# base.net
KiCad netlist of a schematic drawn in EAGLE
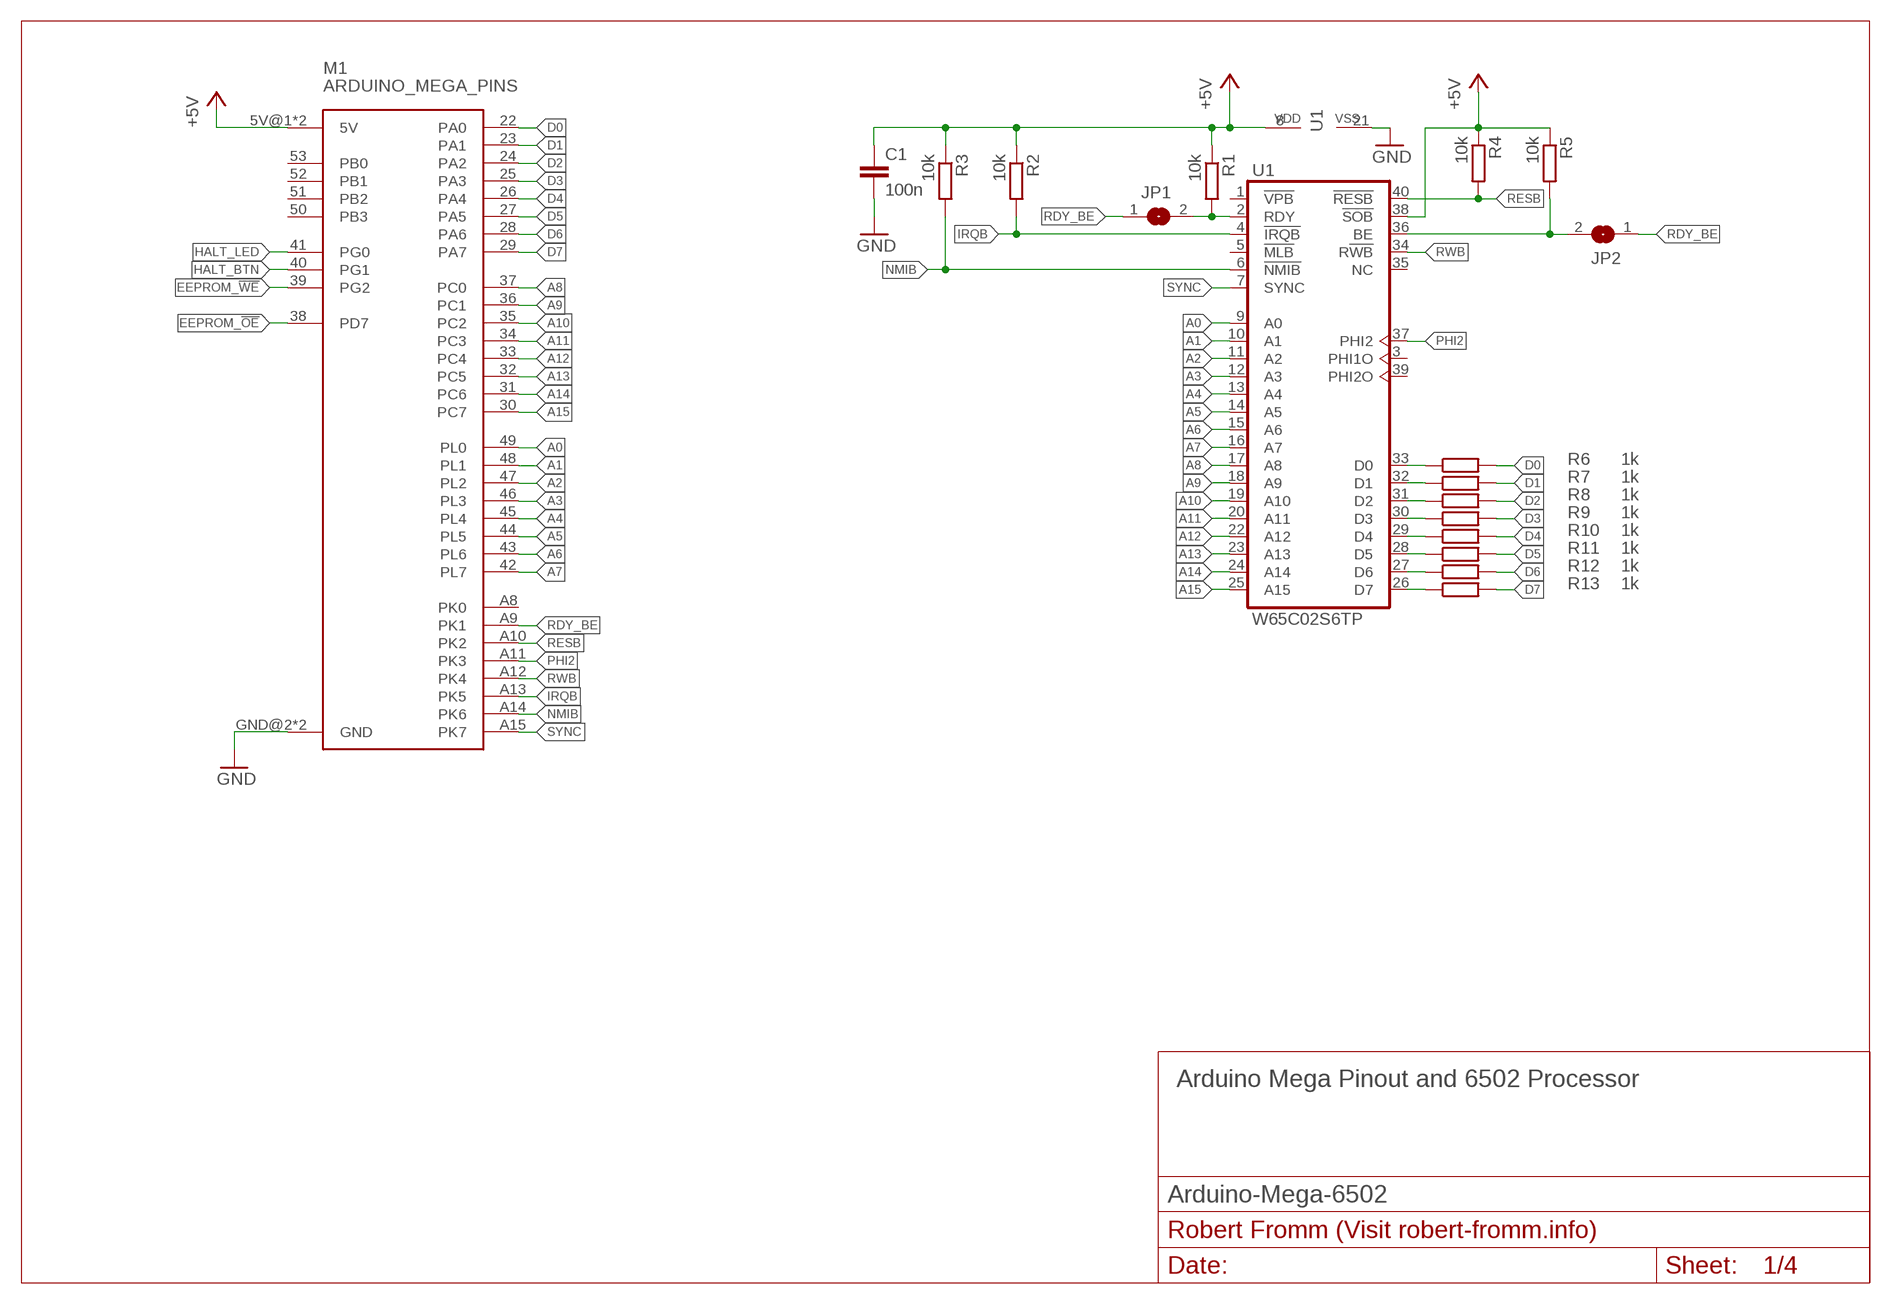
[diagram p0: schematic, sheet 1]
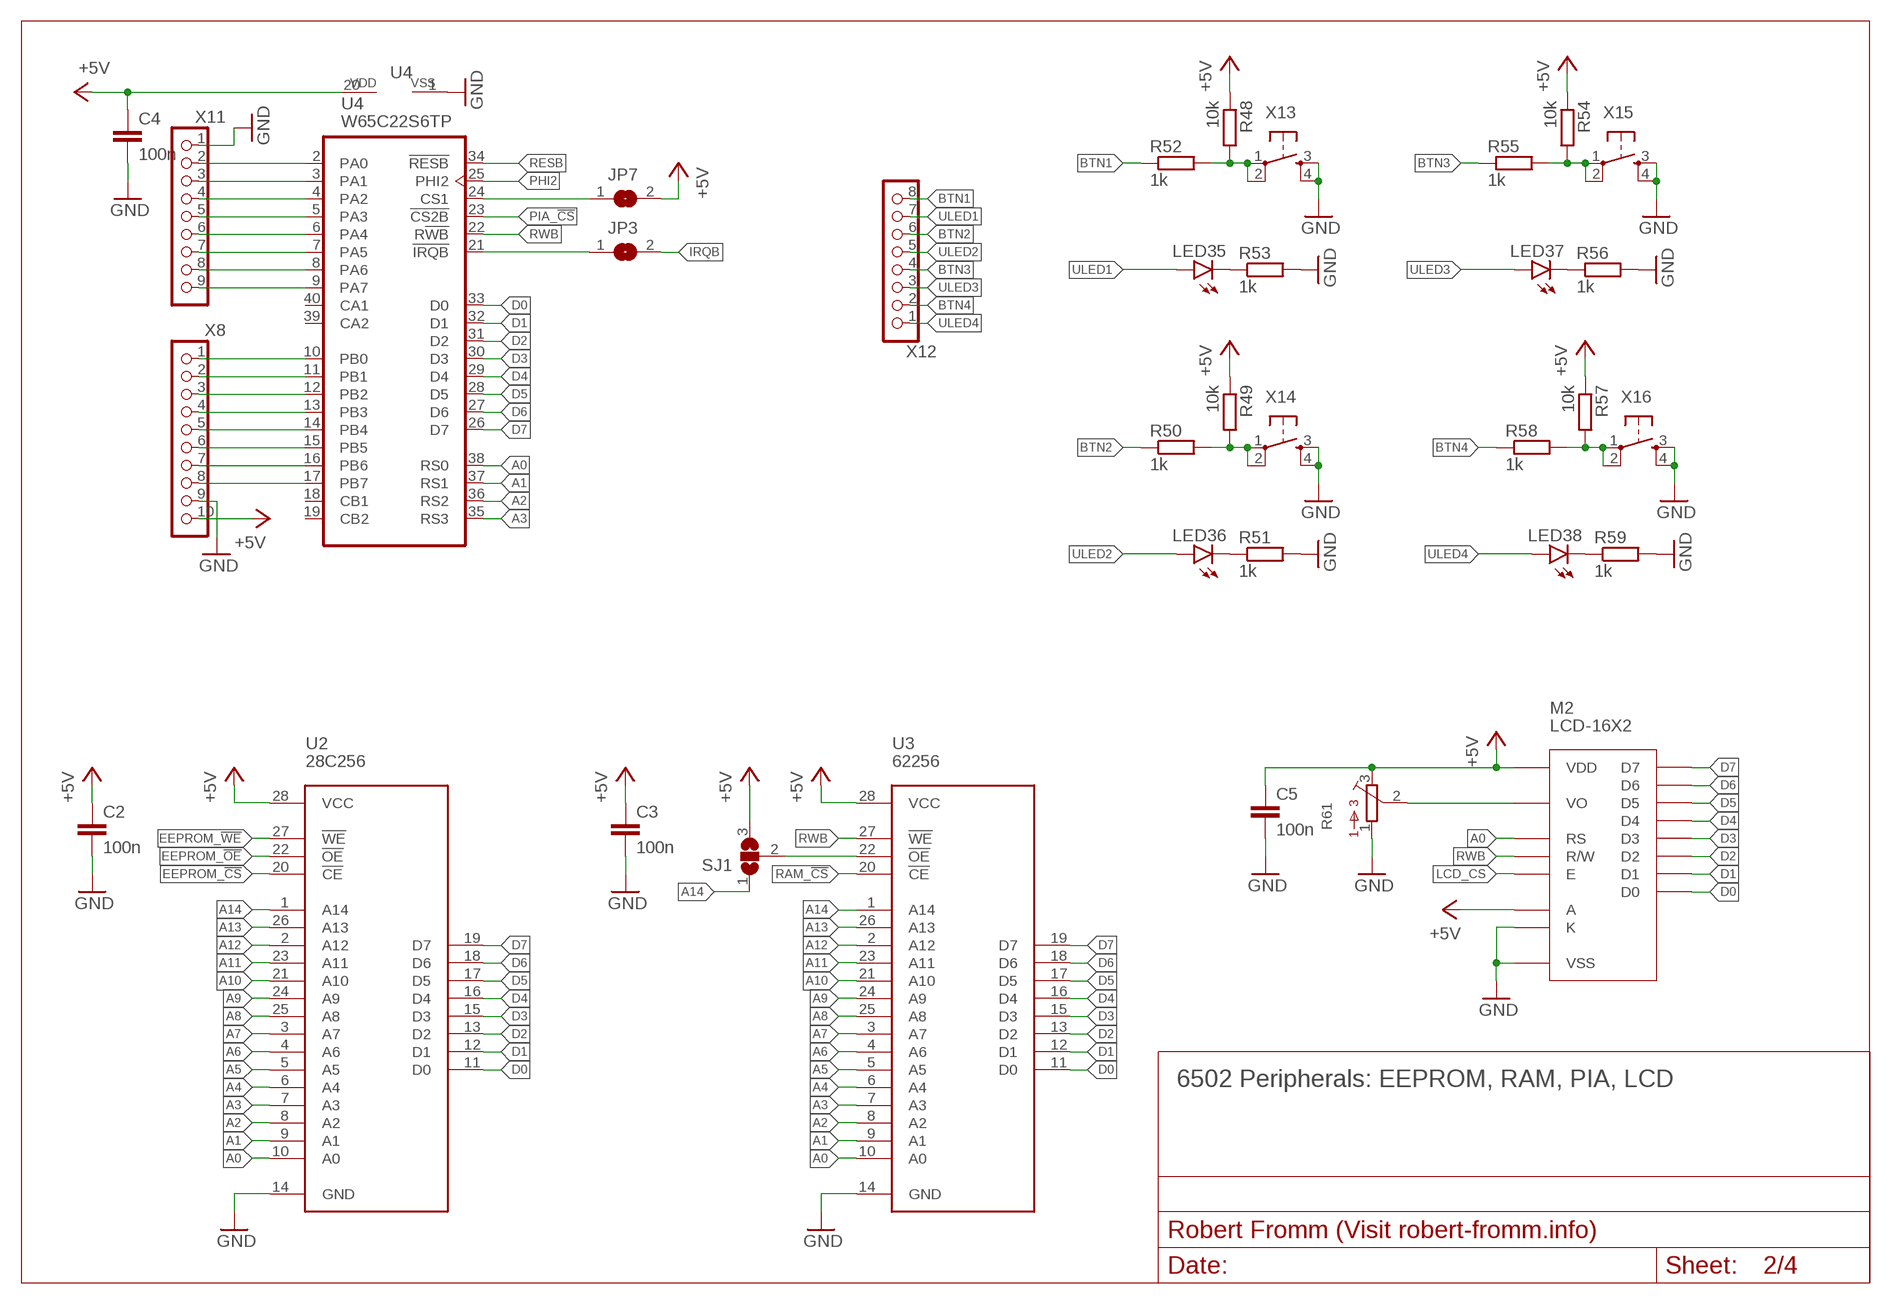
[diagram p1: schematic, sheet 2]
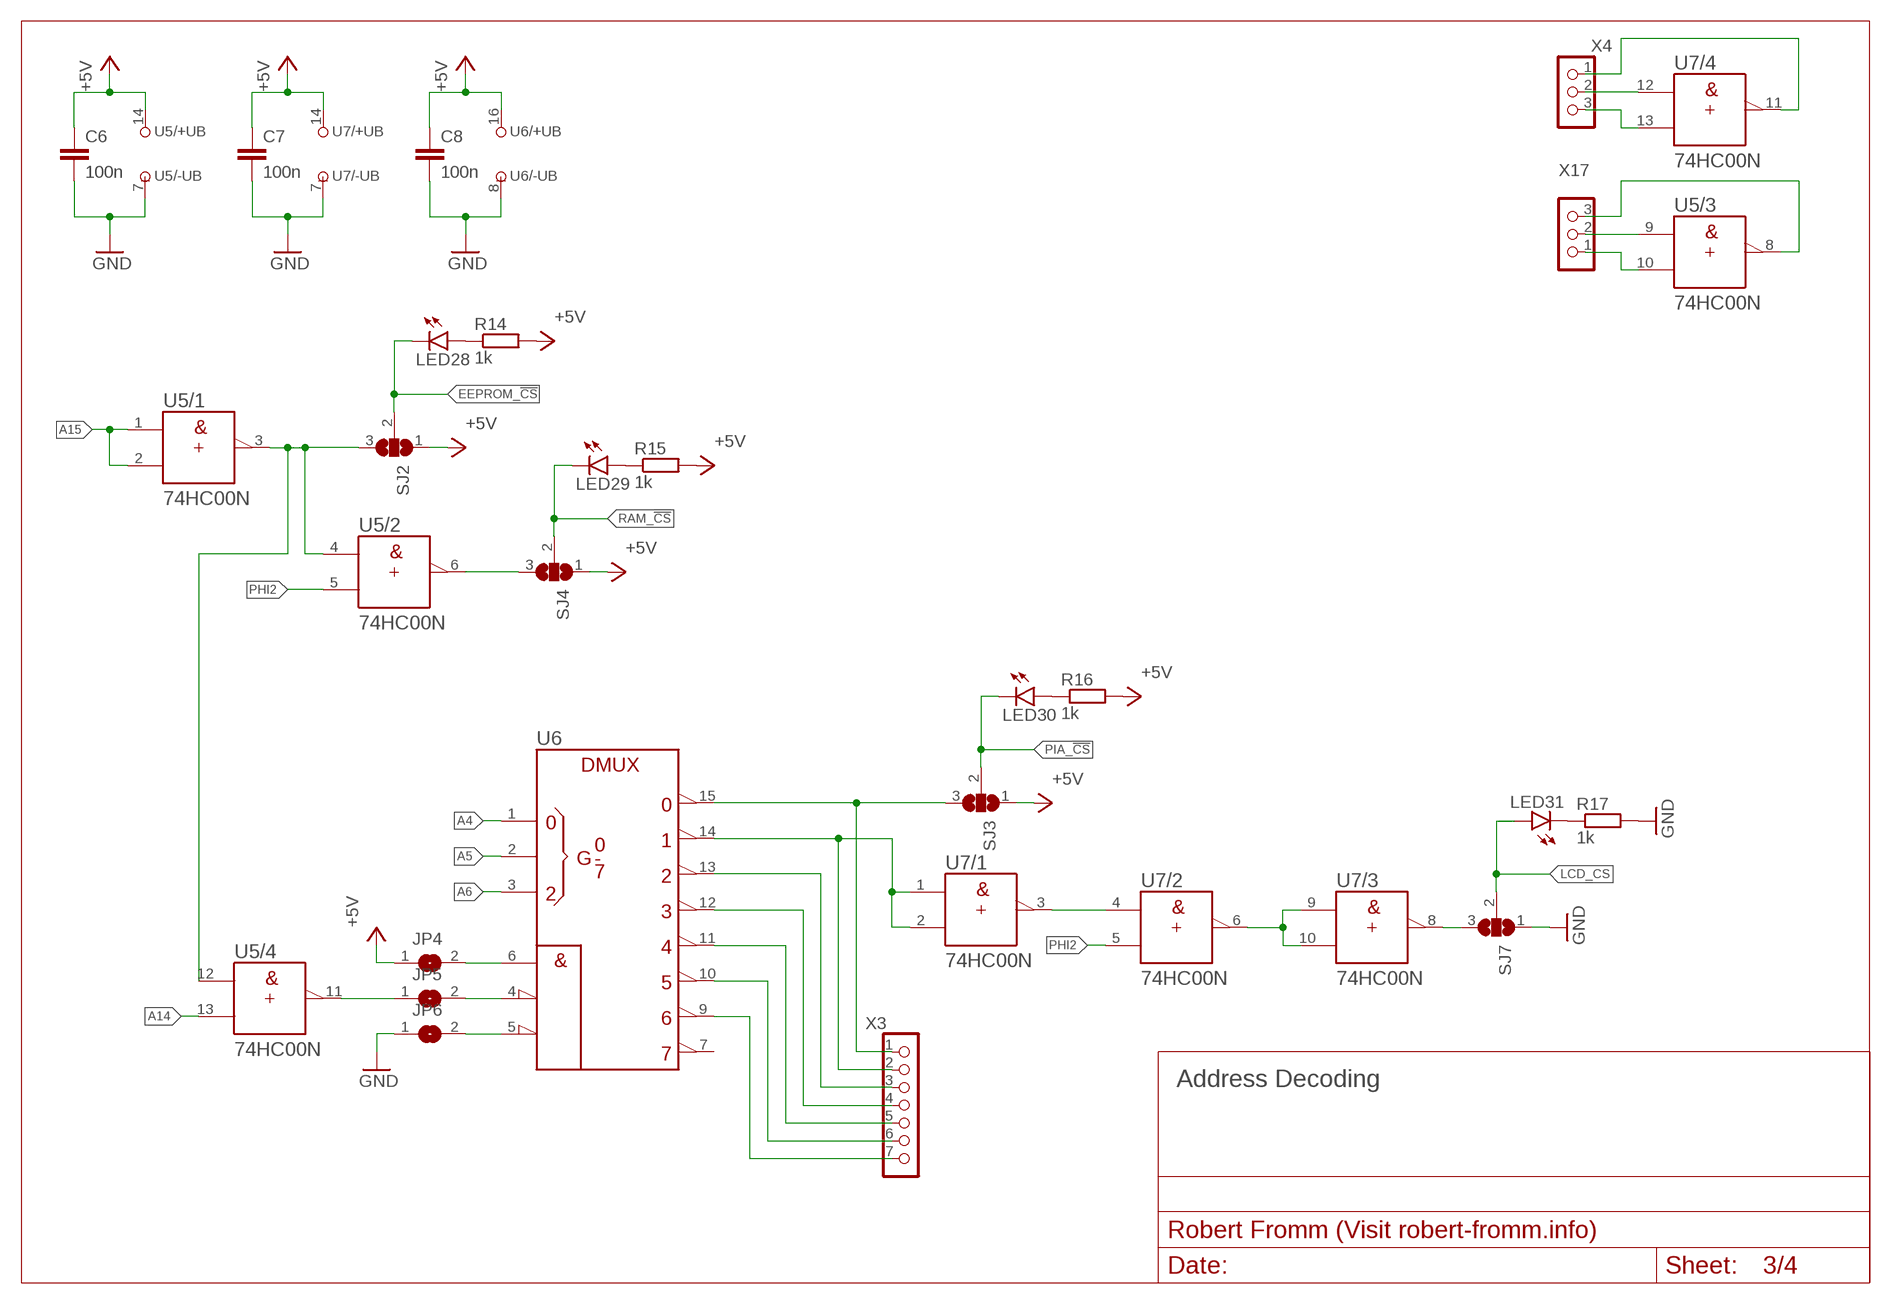
[diagram p2: schematic, sheet 3]
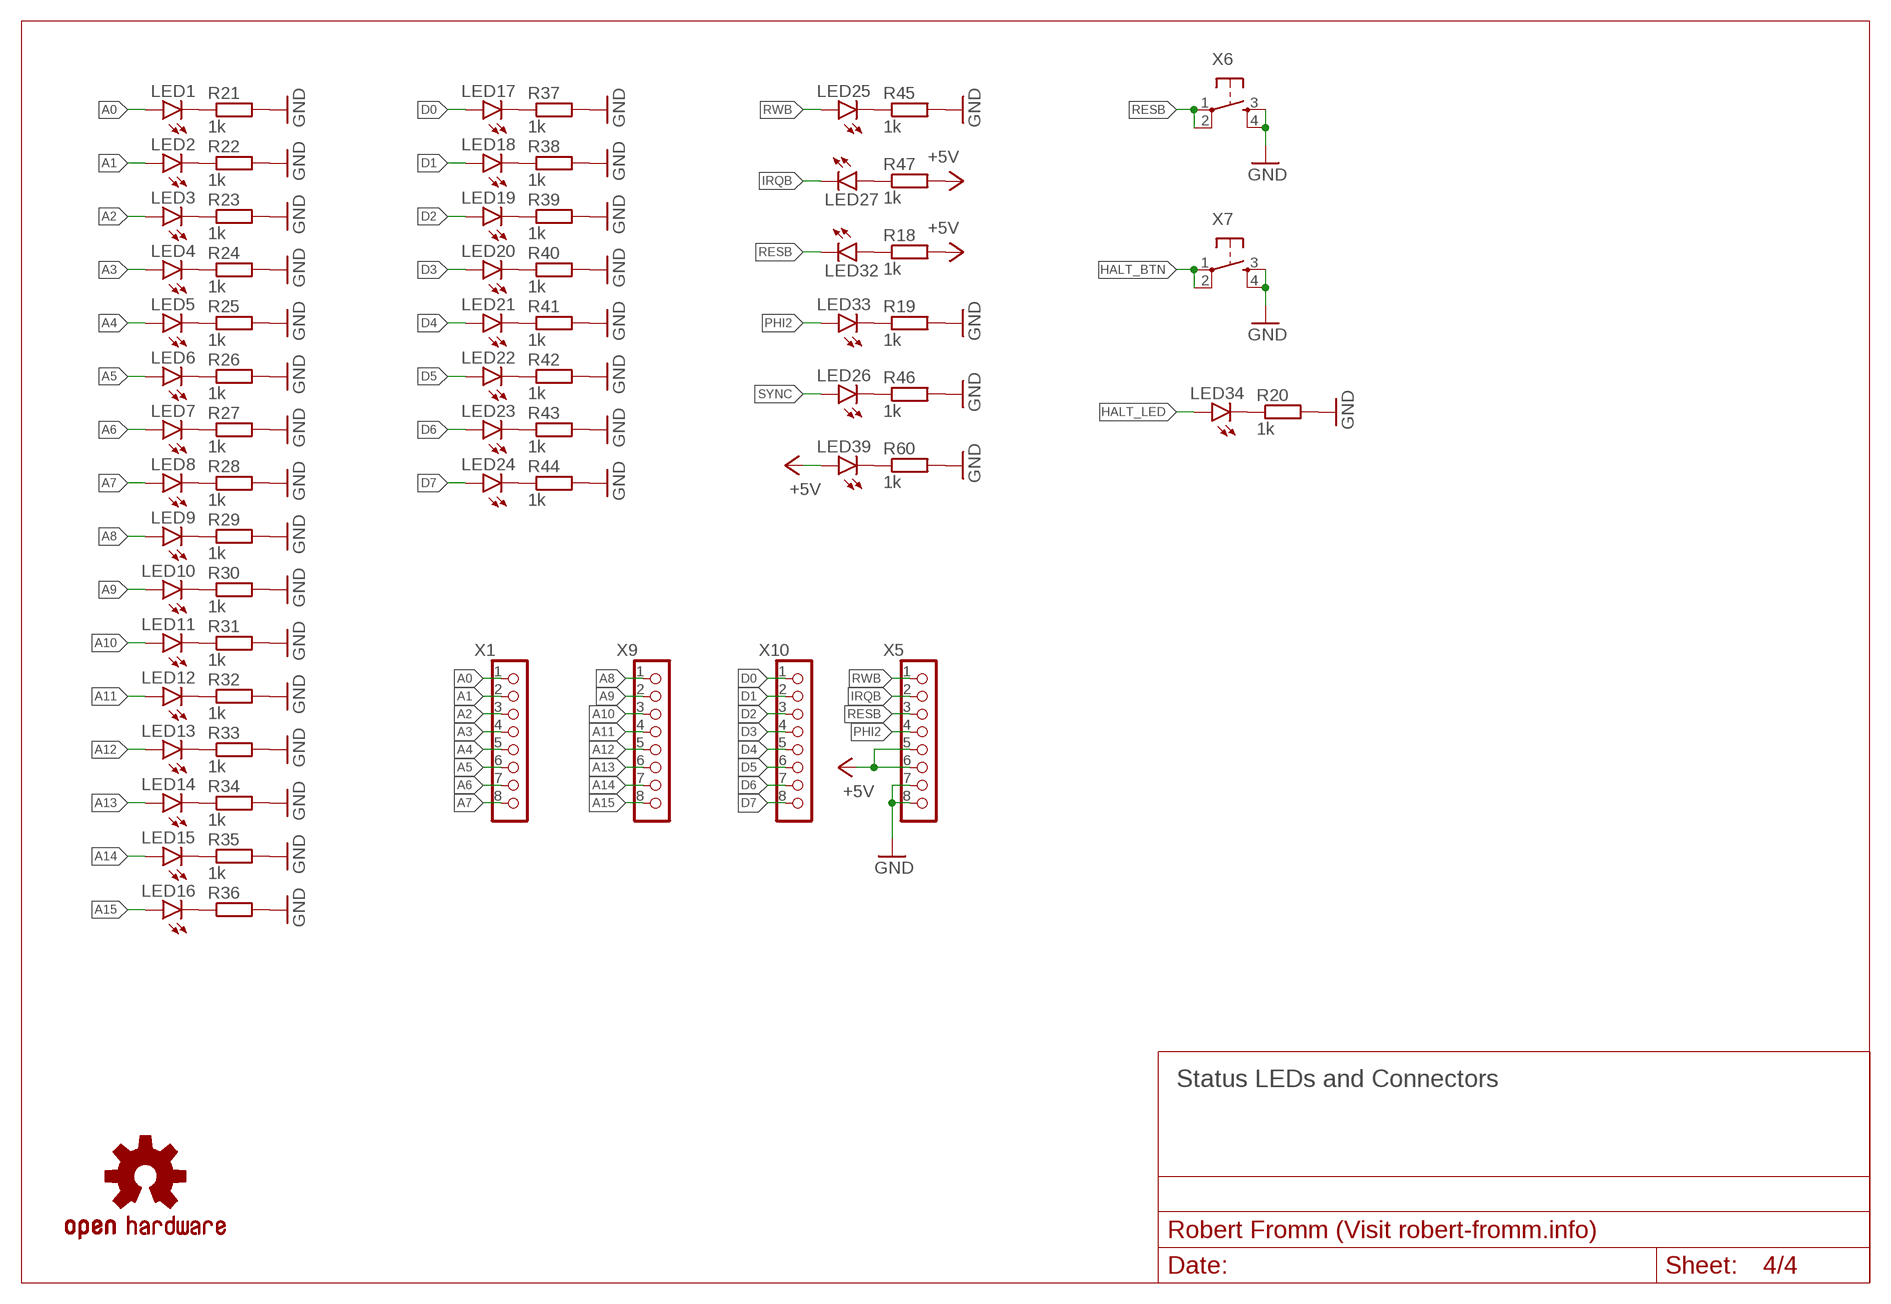
[diagram p3: schematic, sheet 4]

(export (version "E")
  (design (tool "Eeschema 10.0.6"))
  (components
    (comp (ref "C6")
      (value "100n")
      (footprint "eagle-import:C0805")
      (libsource (lib "eagle-import") (part "C-EUC0805"))
    )
    (comp (ref "C7")
      (value "100n")
      (footprint "eagle-import:C0805")
      (libsource (lib "eagle-import") (part "C-EUC0805"))
    )
    (comp (ref "C8")
      (value "100n")
      (footprint "eagle-import:C0805")
      (libsource (lib "eagle-import") (part "C-EUC0805"))
    )
    (comp (ref "JP4") (value "SJ") (footprint "eagle-import:SJ") (libsource (lib "eagle-import") (part "SJ")))
    (comp (ref "JP5") (value "SJ") (footprint "eagle-import:SJ") (libsource (lib "eagle-import") (part "SJ")))
    (comp (ref "JP6") (value "SJ") (footprint "eagle-import:SJ") (libsource (lib "eagle-import") (part "SJ")))
    (comp (ref "LED28")
      (value "LEDSML0805")
      (footprint "eagle-import:SML0805")
      (libsource (lib "eagle-import") (part "LEDSML0805"))
    )
    (comp (ref "LED29")
      (value "LEDSML0805")
      (footprint "eagle-import:SML0805")
      (libsource (lib "eagle-import") (part "LEDSML0805"))
    )
    (comp (ref "LED30")
      (value "LEDSML0805")
      (footprint "eagle-import:SML0805")
      (libsource (lib "eagle-import") (part "LEDSML0805"))
    )
    (comp (ref "LED31")
      (value "LEDSML0805")
      (footprint "eagle-import:SML0805")
      (libsource (lib "eagle-import") (part "LEDSML0805"))
    )
    (comp (ref "R14")
      (value "1k")
      (footprint "eagle-import:R0805")
      (libsource (lib "eagle-import") (part "R-EU_R0805"))
    )
    (comp (ref "R15")
      (value "1k")
      (footprint "eagle-import:R0805")
      (libsource (lib "eagle-import") (part "R-EU_R0805"))
    )
    (comp (ref "R16")
      (value "1k")
      (footprint "eagle-import:R0805")
      (libsource (lib "eagle-import") (part "R-EU_R0805"))
    )
    (comp (ref "R17")
      (value "1k")
      (footprint "eagle-import:R0805")
      (libsource (lib "eagle-import") (part "R-EU_R0805"))
    )
    (comp (ref "SJ2")
      (value "SJ2W")
      (footprint "eagle-import:SJ_2")
      (libsource (lib "eagle-import") (part "SJ2W"))
    )
    (comp (ref "SJ3")
      (value "SJ2W")
      (footprint "eagle-import:SJ_2")
      (libsource (lib "eagle-import") (part "SJ2W"))
    )
    (comp (ref "SJ4")
      (value "SJ2W")
      (footprint "eagle-import:SJ_2")
      (libsource (lib "eagle-import") (part "SJ2W"))
    )
    (comp (ref "SJ7")
      (value "SJ2W")
      (footprint "eagle-import:SJ_2")
      (libsource (lib "eagle-import") (part "SJ2W"))
    )
    (comp (ref "U5")
      (value "74HC00N")
      (footprint "eagle-import:DIL14")
      (libsource (lib "eagle-import") (part "7400NHC"))
    )
    (comp (ref "U6")
      (value "74138N")
      (footprint "eagle-import:DIL16")
      (libsource (lib "eagle-import") (part "74138N"))
    )
    (comp (ref "U7")
      (value "74HC00N")
      (footprint "eagle-import:DIL14")
      (libsource (lib "eagle-import") (part "7400NHC"))
    )
    (comp (ref "X3")
      (value "PINHD_7_RND")
      (footprint "eagle-import:1X07")
      (libsource (lib "eagle-import") (part "PINHD_7_RND"))
    )
    (comp (ref "X4")
      (value "PINHD_3_RND")
      (footprint "eagle-import:1X03")
      (libsource (lib "eagle-import") (part "PINHD_3_RND"))
    )
    (comp (ref "X17")
      (value "PINHD_3_RND")
      (footprint "eagle-import:1X03")
      (libsource (lib "eagle-import") (part "PINHD_3_RND"))
    )
    (comp (ref "LED1")
      (value "LEDSML0805")
      (footprint "eagle-import:SML0805")
      (libsource (lib "eagle-import") (part "LEDSML0805"))
    )
    (comp (ref "LED2")
      (value "LEDSML0805")
      (footprint "eagle-import:SML0805")
      (libsource (lib "eagle-import") (part "LEDSML0805"))
    )
    (comp (ref "LED3")
      (value "LEDSML0805")
      (footprint "eagle-import:SML0805")
      (libsource (lib "eagle-import") (part "LEDSML0805"))
    )
    (comp (ref "LED4")
      (value "LEDSML0805")
      (footprint "eagle-import:SML0805")
      (libsource (lib "eagle-import") (part "LEDSML0805"))
    )
    (comp (ref "LED5")
      (value "LEDSML0805")
      (footprint "eagle-import:SML0805")
      (libsource (lib "eagle-import") (part "LEDSML0805"))
    )
    (comp (ref "LED6")
      (value "LEDSML0805")
      (footprint "eagle-import:SML0805")
      (libsource (lib "eagle-import") (part "LEDSML0805"))
    )
    (comp (ref "LED7")
      (value "LEDSML0805")
      (footprint "eagle-import:SML0805")
      (libsource (lib "eagle-import") (part "LEDSML0805"))
    )
    (comp (ref "LED8")
      (value "LEDSML0805")
      (footprint "eagle-import:SML0805")
      (libsource (lib "eagle-import") (part "LEDSML0805"))
    )
    (comp (ref "LED9")
      (value "LEDSML0805")
      (footprint "eagle-import:SML0805")
      (libsource (lib "eagle-import") (part "LEDSML0805"))
    )
    (comp (ref "LED10")
      (value "LEDSML0805")
      (footprint "eagle-import:SML0805")
      (libsource (lib "eagle-import") (part "LEDSML0805"))
    )
    (comp (ref "LED11")
      (value "LEDSML0805")
      (footprint "eagle-import:SML0805")
      (libsource (lib "eagle-import") (part "LEDSML0805"))
    )
    (comp (ref "LED12")
      (value "LEDSML0805")
      (footprint "eagle-import:SML0805")
      (libsource (lib "eagle-import") (part "LEDSML0805"))
    )
    (comp (ref "LED13")
      (value "LEDSML0805")
      (footprint "eagle-import:SML0805")
      (libsource (lib "eagle-import") (part "LEDSML0805"))
    )
    (comp (ref "LED14")
      (value "LEDSML0805")
      (footprint "eagle-import:SML0805")
      (libsource (lib "eagle-import") (part "LEDSML0805"))
    )
    (comp (ref "LED15")
      (value "LEDSML0805")
      (footprint "eagle-import:SML0805")
      (libsource (lib "eagle-import") (part "LEDSML0805"))
    )
    (comp (ref "LED16")
      (value "LEDSML0805")
      (footprint "eagle-import:SML0805")
      (libsource (lib "eagle-import") (part "LEDSML0805"))
    )
    (comp (ref "LED17")
      (value "LEDSML0805")
      (footprint "eagle-import:SML0805")
      (libsource (lib "eagle-import") (part "LEDSML0805"))
    )
    (comp (ref "LED18")
      (value "LEDSML0805")
      (footprint "eagle-import:SML0805")
      (libsource (lib "eagle-import") (part "LEDSML0805"))
    )
    (comp (ref "LED19")
      (value "LEDSML0805")
      (footprint "eagle-import:SML0805")
      (libsource (lib "eagle-import") (part "LEDSML0805"))
    )
    (comp (ref "LED20")
      (value "LEDSML0805")
      (footprint "eagle-import:SML0805")
      (libsource (lib "eagle-import") (part "LEDSML0805"))
    )
    (comp (ref "LED21")
      (value "LEDSML0805")
      (footprint "eagle-import:SML0805")
      (libsource (lib "eagle-import") (part "LEDSML0805"))
    )
    (comp (ref "LED22")
      (value "LEDSML0805")
      (footprint "eagle-import:SML0805")
      (libsource (lib "eagle-import") (part "LEDSML0805"))
    )
    (comp (ref "LED23")
      (value "LEDSML0805")
      (footprint "eagle-import:SML0805")
      (libsource (lib "eagle-import") (part "LEDSML0805"))
    )
    (comp (ref "LED24")
      (value "LEDSML0805")
      (footprint "eagle-import:SML0805")
      (libsource (lib "eagle-import") (part "LEDSML0805"))
    )
    (comp (ref "LED25")
      (value "LEDSML0805")
      (footprint "eagle-import:SML0805")
      (libsource (lib "eagle-import") (part "LEDSML0805"))
    )
    (comp (ref "LED26")
      (value "LEDSML0805")
      (footprint "eagle-import:SML0805")
      (libsource (lib "eagle-import") (part "LEDSML0805"))
    )
    (comp (ref "LED27")
      (value "LEDSML0805")
      (footprint "eagle-import:SML0805")
      (libsource (lib "eagle-import") (part "LEDSML0805"))
    )
    (comp (ref "LED32")
      (value "LEDSML0805")
      (footprint "eagle-import:SML0805")
      (libsource (lib "eagle-import") (part "LEDSML0805"))
    )
    (comp (ref "LED33")
      (value "LEDSML0805")
      (footprint "eagle-import:SML0805")
      (libsource (lib "eagle-import") (part "LEDSML0805"))
    )
    (comp (ref "LED34")
      (value "LEDSML0805")
      (footprint "eagle-import:SML0805")
      (libsource (lib "eagle-import") (part "LEDSML0805"))
    )
    (comp (ref "LED39")
      (value "LEDSML0805")
      (footprint "eagle-import:SML0805")
      (libsource (lib "eagle-import") (part "LEDSML0805"))
    )
    (comp (ref "LOGO1")
      (value "OSHW-LOGOM")
      (footprint "eagle-import:OSHW-LOGO-M")
      (libsource (lib "eagle-import") (part "OSHW-LOGOM"))
    )
    (comp (ref "R18")
      (value "1k")
      (footprint "eagle-import:R0805")
      (libsource (lib "eagle-import") (part "R-EU_R0805"))
    )
    (comp (ref "R19")
      (value "1k")
      (footprint "eagle-import:R0805")
      (libsource (lib "eagle-import") (part "R-EU_R0805"))
    )
    (comp (ref "R20")
      (value "1k")
      (footprint "eagle-import:R0805")
      (libsource (lib "eagle-import") (part "R-EU_R0805"))
    )
    (comp (ref "R21")
      (value "1k")
      (footprint "eagle-import:R0805")
      (libsource (lib "eagle-import") (part "R-EU_R0805"))
    )
    (comp (ref "R22")
      (value "1k")
      (footprint "eagle-import:R0805")
      (libsource (lib "eagle-import") (part "R-EU_R0805"))
    )
    (comp (ref "R23")
      (value "1k")
      (footprint "eagle-import:R0805")
      (libsource (lib "eagle-import") (part "R-EU_R0805"))
    )
    (comp (ref "R24")
      (value "1k")
      (footprint "eagle-import:R0805")
      (libsource (lib "eagle-import") (part "R-EU_R0805"))
    )
    (comp (ref "R25")
      (value "1k")
      (footprint "eagle-import:R0805")
      (libsource (lib "eagle-import") (part "R-EU_R0805"))
    )
    (comp (ref "R26")
      (value "1k")
      (footprint "eagle-import:R0805")
      (libsource (lib "eagle-import") (part "R-EU_R0805"))
    )
    (comp (ref "R27")
      (value "1k")
      (footprint "eagle-import:R0805")
      (libsource (lib "eagle-import") (part "R-EU_R0805"))
    )
    (comp (ref "R28")
      (value "1k")
      (footprint "eagle-import:R0805")
      (libsource (lib "eagle-import") (part "R-EU_R0805"))
    )
    (comp (ref "R29")
      (value "1k")
      (footprint "eagle-import:R0805")
      (libsource (lib "eagle-import") (part "R-EU_R0805"))
    )
    (comp (ref "R30")
      (value "1k")
      (footprint "eagle-import:R0805")
      (libsource (lib "eagle-import") (part "R-EU_R0805"))
    )
    (comp (ref "R31")
      (value "1k")
      (footprint "eagle-import:R0805")
      (libsource (lib "eagle-import") (part "R-EU_R0805"))
    )
    (comp (ref "R32")
      (value "1k")
      (footprint "eagle-import:R0805")
      (libsource (lib "eagle-import") (part "R-EU_R0805"))
    )
    (comp (ref "R33")
      (value "1k")
      (footprint "eagle-import:R0805")
      (libsource (lib "eagle-import") (part "R-EU_R0805"))
    )
    (comp (ref "R34")
      (value "1k")
      (footprint "eagle-import:R0805")
      (libsource (lib "eagle-import") (part "R-EU_R0805"))
    )
    (comp (ref "R35")
      (value "1k")
      (footprint "eagle-import:R0805")
      (libsource (lib "eagle-import") (part "R-EU_R0805"))
    )
    (comp (ref "R36")
      (value "1k")
      (footprint "eagle-import:R0805")
      (libsource (lib "eagle-import") (part "R-EU_R0805"))
    )
    (comp (ref "R37")
      (value "1k")
      (footprint "eagle-import:R0805")
      (libsource (lib "eagle-import") (part "R-EU_R0805"))
    )
    (comp (ref "R38")
      (value "1k")
      (footprint "eagle-import:R0805")
      (libsource (lib "eagle-import") (part "R-EU_R0805"))
    )
    (comp (ref "R39")
      (value "1k")
      (footprint "eagle-import:R0805")
      (libsource (lib "eagle-import") (part "R-EU_R0805"))
    )
    (comp (ref "R40")
      (value "1k")
      (footprint "eagle-import:R0805")
      (libsource (lib "eagle-import") (part "R-EU_R0805"))
    )
    (comp (ref "R41")
      (value "1k")
      (footprint "eagle-import:R0805")
      (libsource (lib "eagle-import") (part "R-EU_R0805"))
    )
    (comp (ref "R42")
      (value "1k")
      (footprint "eagle-import:R0805")
      (libsource (lib "eagle-import") (part "R-EU_R0805"))
    )
    (comp (ref "R43")
      (value "1k")
      (footprint "eagle-import:R0805")
      (libsource (lib "eagle-import") (part "R-EU_R0805"))
    )
    (comp (ref "R44")
      (value "1k")
      (footprint "eagle-import:R0805")
      (libsource (lib "eagle-import") (part "R-EU_R0805"))
    )
    (comp (ref "R45")
      (value "1k")
      (footprint "eagle-import:R0805")
      (libsource (lib "eagle-import") (part "R-EU_R0805"))
    )
    (comp (ref "R46")
      (value "1k")
      (footprint "eagle-import:R0805")
      (libsource (lib "eagle-import") (part "R-EU_R0805"))
    )
    (comp (ref "R47")
      (value "1k")
      (footprint "eagle-import:R0805")
      (libsource (lib "eagle-import") (part "R-EU_R0805"))
    )
    (comp (ref "R60")
      (value "1k")
      (footprint "eagle-import:R0805")
      (libsource (lib "eagle-import") (part "R-EU_R0805"))
    )
    (comp (ref "X1")
      (value "PINHD_8_RND")
      (footprint "eagle-import:1X08")
      (libsource (lib "eagle-import") (part "PINHD_8_RND"))
    )
    (comp (ref "X5")
      (value "PINHD_8_RND")
      (footprint "eagle-import:1X08")
      (libsource (lib "eagle-import") (part "PINHD_8_RND"))
    )
    (comp (ref "X6")
      (value "TACT_SWITCH")
      (footprint "eagle-import:TACTILE_SWITCH_PTH_6.0MM")
      (libsource (lib "eagle-import") (part "TACT_SWITCH"))
    )
    (comp (ref "X7")
      (value "TACT_SWITCH")
      (footprint "eagle-import:TACTILE_SWITCH_PTH_6.0MM")
      (libsource (lib "eagle-import") (part "TACT_SWITCH"))
    )
    (comp (ref "X9")
      (value "PINHD_8_RND")
      (footprint "eagle-import:1X08")
      (libsource (lib "eagle-import") (part "PINHD_8_RND"))
    )
    (comp (ref "X10")
      (value "PINHD_8_RND")
      (footprint "eagle-import:1X08")
      (libsource (lib "eagle-import") (part "PINHD_8_RND"))
    )
    (comp (ref "C1")
      (value "100n")
      (footprint "eagle-import:C0805")
      (libsource (lib "eagle-import") (part "C-EUC0805"))
    )
    (comp (ref "JP1") (value "SJ") (footprint "eagle-import:SJ") (libsource (lib "eagle-import") (part "SJ")))
    (comp (ref "JP2") (value "SJ") (footprint "eagle-import:SJ") (libsource (lib "eagle-import") (part "SJ")))
    (comp (ref "M1")
      (value "ARDUINO_MEGA_PINS")
      (footprint "eagle-import:ARDUINO_MEGA_PINS")
      (libsource (lib "eagle-import") (part "ARDUINO_MEGA_PINS"))
    )
    (comp (ref "R1")
      (value "10k")
      (footprint "eagle-import:R0805")
      (libsource (lib "eagle-import") (part "R-EU_R0805"))
    )
    (comp (ref "R2")
      (value "10k")
      (footprint "eagle-import:R0805")
      (libsource (lib "eagle-import") (part "R-EU_R0805"))
    )
    (comp (ref "R3")
      (value "10k")
      (footprint "eagle-import:R0805")
      (libsource (lib "eagle-import") (part "R-EU_R0805"))
    )
    (comp (ref "R4")
      (value "10k")
      (footprint "eagle-import:R0805")
      (libsource (lib "eagle-import") (part "R-EU_R0805"))
    )
    (comp (ref "R5")
      (value "10k")
      (footprint "eagle-import:R0805")
      (libsource (lib "eagle-import") (part "R-EU_R0805"))
    )
    (comp (ref "R6")
      (value "1k")
      (footprint "eagle-import:R0805")
      (libsource (lib "eagle-import") (part "R-EU_R0805"))
    )
    (comp (ref "R7")
      (value "1k")
      (footprint "eagle-import:R0805")
      (libsource (lib "eagle-import") (part "R-EU_R0805"))
    )
    (comp (ref "R8")
      (value "1k")
      (footprint "eagle-import:R0805")
      (libsource (lib "eagle-import") (part "R-EU_R0805"))
    )
    (comp (ref "R9")
      (value "1k")
      (footprint "eagle-import:R0805")
      (libsource (lib "eagle-import") (part "R-EU_R0805"))
    )
    (comp (ref "R10")
      (value "1k")
      (footprint "eagle-import:R0805")
      (libsource (lib "eagle-import") (part "R-EU_R0805"))
    )
    (comp (ref "R11")
      (value "1k")
      (footprint "eagle-import:R0805")
      (libsource (lib "eagle-import") (part "R-EU_R0805"))
    )
    (comp (ref "R12")
      (value "1k")
      (footprint "eagle-import:R0805")
      (libsource (lib "eagle-import") (part "R-EU_R0805"))
    )
    (comp (ref "R13")
      (value "1k")
      (footprint "eagle-import:R0805")
      (libsource (lib "eagle-import") (part "R-EU_R0805"))
    )
    (comp (ref "U1")
      (value "W65C02S6TP")
      (footprint "eagle-import:DIL40")
      (libsource (lib "eagle-import") (part "W65C02SP6T"))
    )
    (comp (ref "C2")
      (value "100n")
      (footprint "eagle-import:C0805")
      (libsource (lib "eagle-import") (part "C-EUC0805"))
    )
    (comp (ref "C3")
      (value "100n")
      (footprint "eagle-import:C0805")
      (libsource (lib "eagle-import") (part "C-EUC0805"))
    )
    (comp (ref "C4")
      (value "100n")
      (footprint "eagle-import:C0805")
      (libsource (lib "eagle-import") (part "C-EUC0805"))
    )
    (comp (ref "C5")
      (value "100n")
      (footprint "eagle-import:C0805")
      (libsource (lib "eagle-import") (part "C-EUC0805"))
    )
    (comp (ref "JP3") (value "SJ") (footprint "eagle-import:SJ") (libsource (lib "eagle-import") (part "SJ")))
    (comp (ref "JP7") (value "SJ") (footprint "eagle-import:SJ") (libsource (lib "eagle-import") (part "SJ")))
    (comp (ref "LED35")
      (value "LEDSML0805")
      (footprint "eagle-import:SML0805")
      (libsource (lib "eagle-import") (part "LEDSML0805"))
    )
    (comp (ref "LED36")
      (value "LEDSML0805")
      (footprint "eagle-import:SML0805")
      (libsource (lib "eagle-import") (part "LEDSML0805"))
    )
    (comp (ref "LED37")
      (value "LEDSML0805")
      (footprint "eagle-import:SML0805")
      (libsource (lib "eagle-import") (part "LEDSML0805"))
    )
    (comp (ref "LED38")
      (value "LEDSML0805")
      (footprint "eagle-import:SML0805")
      (libsource (lib "eagle-import") (part "LEDSML0805"))
    )
    (comp (ref "M2")
      (value "LCD-16X2")
      (footprint "eagle-import:LCD-16X2")
      (libsource (lib "eagle-import") (part "LCD-16X2"))
    )
    (comp (ref "R48")
      (value "10k")
      (footprint "eagle-import:R0805")
      (libsource (lib "eagle-import") (part "R-EU_R0805"))
    )
    (comp (ref "R49")
      (value "10k")
      (footprint "eagle-import:R0805")
      (libsource (lib "eagle-import") (part "R-EU_R0805"))
    )
    (comp (ref "R50")
      (value "1k")
      (footprint "eagle-import:R0805")
      (libsource (lib "eagle-import") (part "R-EU_R0805"))
    )
    (comp (ref "R51")
      (value "1k")
      (footprint "eagle-import:R0805")
      (libsource (lib "eagle-import") (part "R-EU_R0805"))
    )
    (comp (ref "R52")
      (value "1k")
      (footprint "eagle-import:R0805")
      (libsource (lib "eagle-import") (part "R-EU_R0805"))
    )
    (comp (ref "R53")
      (value "1k")
      (footprint "eagle-import:R0805")
      (libsource (lib "eagle-import") (part "R-EU_R0805"))
    )
    (comp (ref "R54")
      (value "10k")
      (footprint "eagle-import:R0805")
      (libsource (lib "eagle-import") (part "R-EU_R0805"))
    )
    (comp (ref "R55")
      (value "1k")
      (footprint "eagle-import:R0805")
      (libsource (lib "eagle-import") (part "R-EU_R0805"))
    )
    (comp (ref "R56")
      (value "1k")
      (footprint "eagle-import:R0805")
      (libsource (lib "eagle-import") (part "R-EU_R0805"))
    )
    (comp (ref "R57")
      (value "10k")
      (footprint "eagle-import:R0805")
      (libsource (lib "eagle-import") (part "R-EU_R0805"))
    )
    (comp (ref "R58")
      (value "1k")
      (footprint "eagle-import:R0805")
      (libsource (lib "eagle-import") (part "R-EU_R0805"))
    )
    (comp (ref "R59")
      (value "1k")
      (footprint "eagle-import:R0805")
      (libsource (lib "eagle-import") (part "R-EU_R0805"))
    )
    (comp (ref "R61")
      (value "3362P")
      (footprint "eagle-import:3362P")
      (libsource (lib "eagle-import") (part "3362P"))
    )
    (comp (ref "SJ1")
      (value "SJ2W")
      (footprint "eagle-import:SJ_2")
      (libsource (lib "eagle-import") (part "SJ2W"))
    )
    (comp (ref "U2")
      (value "28C256")
      (footprint "eagle-import:DIL28-6")
      (libsource (lib "eagle-import") (part "28C256"))
    )
    (comp (ref "U3")
      (value "62256")
      (footprint "eagle-import:DIL28-6")
      (libsource (lib "eagle-import") (part "62256"))
    )
    (comp (ref "U4")
      (value "W65C22S6TP")
      (footprint "eagle-import:DIL40")
      (libsource (lib "eagle-import") (part "W65C22SP6T"))
    )
    (comp (ref "X8")
      (value "PINHD_10_RND")
      (footprint "eagle-import:1X10")
      (libsource (lib "eagle-import") (part "PINHD_10_RND"))
    )
    (comp (ref "X11")
      (value "PINHD_9_RND")
      (footprint "eagle-import:1X09")
      (libsource (lib "eagle-import") (part "PINHD_9_RND"))
    )
    (comp (ref "X12")
      (value "PINHD_8_RND")
      (footprint "eagle-import:1X08")
      (libsource (lib "eagle-import") (part "PINHD_8_RND"))
    )
    (comp (ref "X13")
      (value "TACT_SWITCH")
      (footprint "eagle-import:TACTILE_SWITCH_PTH_6.0MM")
      (libsource (lib "eagle-import") (part "TACT_SWITCH"))
    )
    (comp (ref "X14")
      (value "TACT_SWITCH")
      (footprint "eagle-import:TACTILE_SWITCH_PTH_6.0MM")
      (libsource (lib "eagle-import") (part "TACT_SWITCH"))
    )
    (comp (ref "X15")
      (value "TACT_SWITCH")
      (footprint "eagle-import:TACTILE_SWITCH_PTH_6.0MM")
      (libsource (lib "eagle-import") (part "TACT_SWITCH"))
    )
    (comp (ref "X16")
      (value "TACT_SWITCH")
      (footprint "eagle-import:TACTILE_SWITCH_PTH_6.0MM")
      (libsource (lib "eagle-import") (part "TACT_SWITCH"))
    )
  )
  (nets
    (net (code "1") (name "+5V") (class "Default")
      (node (ref "C1") (pin "1") (pinfunction "1_1") (pintype "passive"))
      (node (ref "C2") (pin "1") (pinfunction "1_1") (pintype "passive"))
      (node (ref "C3") (pin "1") (pinfunction "1_1") (pintype "passive"))
      (node (ref "C4") (pin "1") (pinfunction "1_1") (pintype "passive"))
      (node (ref "C5") (pin "1") (pinfunction "1_1") (pintype "passive"))
      (node (ref "C6") (pin "1") (pinfunction "1_1") (pintype "passive"))
      (node (ref "C7") (pin "1") (pinfunction "1_1") (pintype "passive"))
      (node (ref "C8") (pin "1") (pinfunction "1_1") (pintype "passive"))
      (node (ref "JP4") (pin "1") (pinfunction "1_1") (pintype "passive"))
      (node (ref "JP7") (pin "2") (pinfunction "2_2") (pintype "passive"))
      (node (ref "LED39") (pin "A") (pinfunction "A_A") (pintype "passive"))
      (node (ref "M1") (pin "5V@1") (pinfunction "5V_5V@1") (pintype "bidirectional"))
      (node (ref "M1") (pin "5V@2") (pinfunction "5V_5V@2") (pintype "bidirectional"))
      (node (ref "M2") (pin "15") (pinfunction "A_15") (pintype "power_in"))
      (node (ref "M2") (pin "2") (pinfunction "VDD_2") (pintype "power_in"))
      (node (ref "R1") (pin "1") (pinfunction "1_1") (pintype "passive"))
      (node (ref "R14") (pin "2") (pinfunction "2_2") (pintype "passive"))
      (node (ref "R15") (pin "2") (pinfunction "2_2") (pintype "passive"))
      (node (ref "R16") (pin "2") (pinfunction "2_2") (pintype "passive"))
      (node (ref "R18") (pin "2") (pinfunction "2_2") (pintype "passive"))
      (node (ref "R2") (pin "1") (pinfunction "1_1") (pintype "passive"))
      (node (ref "R3") (pin "1") (pinfunction "1_1") (pintype "passive"))
      (node (ref "R4") (pin "1") (pinfunction "1_1") (pintype "passive"))
      (node (ref "R47") (pin "2") (pinfunction "2_2") (pintype "passive"))
      (node (ref "R48") (pin "1") (pinfunction "1_1") (pintype "passive"))
      (node (ref "R49") (pin "1") (pinfunction "1_1") (pintype "passive"))
      (node (ref "R5") (pin "1") (pinfunction "1_1") (pintype "passive"))
      (node (ref "R54") (pin "1") (pinfunction "1_1") (pintype "passive"))
      (node (ref "R57") (pin "1") (pinfunction "1_1") (pintype "passive"))
      (node (ref "R61") (pin "3") (pinfunction "3_3") (pintype "passive"))
      (node (ref "SJ1") (pin "3") (pinfunction "3_3") (pintype "passive"))
      (node (ref "SJ2") (pin "1") (pinfunction "1_1") (pintype "passive"))
      (node (ref "SJ3") (pin "1") (pinfunction "1_1") (pintype "passive"))
      (node (ref "SJ4") (pin "1") (pinfunction "1_1") (pintype "passive"))
      (node (ref "U1") (pin "38") (pinfunction "~{SOB}_38") (pintype "input"))
      (node (ref "U1") (pin "8") (pinfunction "VDD_8") (pintype "power_in"))
      (node (ref "U2") (pin "28") (pinfunction "VCC_28") (pintype "power_in"))
      (node (ref "U3") (pin "28") (pinfunction "VCC_28") (pintype "power_in"))
      (node (ref "U4") (pin "20") (pinfunction "VDD_20") (pintype "power_in"))
      (node (ref "U5") (pin "14") (pinfunction "+UB_14") (pintype "power_in"))
      (node (ref "U6") (pin "16") (pinfunction "+UB_16") (pintype "power_in"))
      (node (ref "U7") (pin "14") (pinfunction "+UB_14") (pintype "power_in"))
      (node (ref "X5") (pin "5") (pinfunction "5_5") (pintype "passive"))
      (node (ref "X5") (pin "6") (pinfunction "6_6") (pintype "passive"))
      (node (ref "X8") (pin "10") (pinfunction "10_10") (pintype "passive"))
    )
    (net (code "2") (name "A0") (class "Default")
      (node (ref "LED1") (pin "A") (pinfunction "A_A") (pintype "passive"))
      (node (ref "M1") (pin "49") (pinfunction "PL0_49") (pintype "bidirectional"))
      (node (ref "M2") (pin "4") (pinfunction "RS_4") (pintype "input"))
      (node (ref "U1") (pin "9") (pinfunction "A0_9") (pintype "output"))
      (node (ref "U2") (pin "10") (pinfunction "A0_10") (pintype "input"))
      (node (ref "U3") (pin "10") (pinfunction "A0_10") (pintype "input"))
      (node (ref "U4") (pin "38") (pinfunction "RS0_38") (pintype "input"))
      (node (ref "X1") (pin "1") (pinfunction "1_1") (pintype "passive"))
    )
    (net (code "3") (name "A1") (class "Default")
      (node (ref "LED2") (pin "A") (pinfunction "A_A") (pintype "passive"))
      (node (ref "M1") (pin "48") (pinfunction "PL1_48") (pintype "bidirectional"))
      (node (ref "U1") (pin "10") (pinfunction "A1_10") (pintype "output"))
      (node (ref "U2") (pin "9") (pinfunction "A1_9") (pintype "input"))
      (node (ref "U3") (pin "9") (pinfunction "A1_9") (pintype "input"))
      (node (ref "U4") (pin "37") (pinfunction "RS1_37") (pintype "input"))
      (node (ref "X1") (pin "2") (pinfunction "2_2") (pintype "passive"))
    )
    (net (code "4") (name "A2") (class "Default")
      (node (ref "LED3") (pin "A") (pinfunction "A_A") (pintype "passive"))
      (node (ref "M1") (pin "47") (pinfunction "PL2_47") (pintype "bidirectional"))
      (node (ref "U1") (pin "11") (pinfunction "A2_11") (pintype "output"))
      (node (ref "U2") (pin "8") (pinfunction "A2_8") (pintype "input"))
      (node (ref "U3") (pin "8") (pinfunction "A2_8") (pintype "input"))
      (node (ref "U4") (pin "36") (pinfunction "RS2_36") (pintype "input"))
      (node (ref "X1") (pin "3") (pinfunction "3_3") (pintype "passive"))
    )
    (net (code "5") (name "A3") (class "Default")
      (node (ref "LED4") (pin "A") (pinfunction "A_A") (pintype "passive"))
      (node (ref "M1") (pin "46") (pinfunction "PL3_46") (pintype "bidirectional"))
      (node (ref "U1") (pin "12") (pinfunction "A3_12") (pintype "output"))
      (node (ref "U2") (pin "7") (pinfunction "A3_7") (pintype "input"))
      (node (ref "U3") (pin "7") (pinfunction "A3_7") (pintype "input"))
      (node (ref "U4") (pin "35") (pinfunction "RS3_35") (pintype "input"))
      (node (ref "X1") (pin "4") (pinfunction "4_4") (pintype "passive"))
    )
    (net (code "6") (name "A4") (class "Default")
      (node (ref "LED5") (pin "A") (pinfunction "A_A") (pintype "passive"))
      (node (ref "M1") (pin "45") (pinfunction "PL4_45") (pintype "bidirectional"))
      (node (ref "U1") (pin "13") (pinfunction "A4_13") (pintype "output"))
      (node (ref "U2") (pin "6") (pinfunction "A4_6") (pintype "input"))
      (node (ref "U3") (pin "6") (pinfunction "A4_6") (pintype "input"))
      (node (ref "U6") (pin "1") (pinfunction "A_1") (pintype "input"))
      (node (ref "X1") (pin "5") (pinfunction "5_5") (pintype "passive"))
    )
    (net (code "7") (name "A5") (class "Default")
      (node (ref "LED6") (pin "A") (pinfunction "A_A") (pintype "passive"))
      (node (ref "M1") (pin "44") (pinfunction "PL5_44") (pintype "bidirectional"))
      (node (ref "U1") (pin "14") (pinfunction "A5_14") (pintype "output"))
      (node (ref "U2") (pin "5") (pinfunction "A5_5") (pintype "input"))
      (node (ref "U3") (pin "5") (pinfunction "A5_5") (pintype "input"))
      (node (ref "U6") (pin "2") (pinfunction "B_2") (pintype "input"))
      (node (ref "X1") (pin "6") (pinfunction "6_6") (pintype "passive"))
    )
    (net (code "8") (name "A6") (class "Default")
      (node (ref "LED7") (pin "A") (pinfunction "A_A") (pintype "passive"))
      (node (ref "M1") (pin "43") (pinfunction "PL6_43") (pintype "bidirectional"))
      (node (ref "U1") (pin "15") (pinfunction "A6_15") (pintype "output"))
      (node (ref "U2") (pin "4") (pinfunction "A6_4") (pintype "input"))
      (node (ref "U3") (pin "4") (pinfunction "A6_4") (pintype "input"))
      (node (ref "U6") (pin "3") (pinfunction "C_3") (pintype "input"))
      (node (ref "X1") (pin "7") (pinfunction "7_7") (pintype "passive"))
    )
    (net (code "9") (name "A7") (class "Default")
      (node (ref "LED8") (pin "A") (pinfunction "A_A") (pintype "passive"))
      (node (ref "M1") (pin "42") (pinfunction "PL7_42") (pintype "bidirectional"))
      (node (ref "U1") (pin "16") (pinfunction "A7_16") (pintype "output"))
      (node (ref "U2") (pin "3") (pinfunction "A7_3") (pintype "input"))
      (node (ref "U3") (pin "3") (pinfunction "A7_3") (pintype "input"))
      (node (ref "X1") (pin "8") (pinfunction "8_8") (pintype "passive"))
    )
    (net (code "10") (name "A8") (class "Default")
      (node (ref "LED9") (pin "A") (pinfunction "A_A") (pintype "passive"))
      (node (ref "M1") (pin "37") (pinfunction "PC0_37") (pintype "bidirectional"))
      (node (ref "U1") (pin "17") (pinfunction "A8_17") (pintype "output"))
      (node (ref "U2") (pin "25") (pinfunction "A8_25") (pintype "input"))
      (node (ref "U3") (pin "25") (pinfunction "A8_25") (pintype "input"))
      (node (ref "X9") (pin "1") (pinfunction "1_1") (pintype "passive"))
    )
    (net (code "11") (name "A9") (class "Default")
      (node (ref "LED10") (pin "A") (pinfunction "A_A") (pintype "passive"))
      (node (ref "M1") (pin "36") (pinfunction "PC1_36") (pintype "bidirectional"))
      (node (ref "U1") (pin "18") (pinfunction "A9_18") (pintype "output"))
      (node (ref "U2") (pin "24") (pinfunction "A9_24") (pintype "input"))
      (node (ref "U3") (pin "24") (pinfunction "A9_24") (pintype "input"))
      (node (ref "X9") (pin "2") (pinfunction "2_2") (pintype "passive"))
    )
    (net (code "12") (name "A10") (class "Default")
      (node (ref "LED11") (pin "A") (pinfunction "A_A") (pintype "passive"))
      (node (ref "M1") (pin "35") (pinfunction "PC2_35") (pintype "bidirectional"))
      (node (ref "U1") (pin "19") (pinfunction "A10_19") (pintype "output"))
      (node (ref "U2") (pin "21") (pinfunction "A10_21") (pintype "input"))
      (node (ref "U3") (pin "21") (pinfunction "A10_21") (pintype "input"))
      (node (ref "X9") (pin "3") (pinfunction "3_3") (pintype "passive"))
    )
    (net (code "13") (name "A11") (class "Default")
      (node (ref "LED12") (pin "A") (pinfunction "A_A") (pintype "passive"))
      (node (ref "M1") (pin "34") (pinfunction "PC3_34") (pintype "bidirectional"))
      (node (ref "U1") (pin "20") (pinfunction "A11_20") (pintype "output"))
      (node (ref "U2") (pin "23") (pinfunction "A11_23") (pintype "input"))
      (node (ref "U3") (pin "23") (pinfunction "A11_23") (pintype "input"))
      (node (ref "X9") (pin "4") (pinfunction "4_4") (pintype "passive"))
    )
    (net (code "14") (name "A12") (class "Default")
      (node (ref "LED13") (pin "A") (pinfunction "A_A") (pintype "passive"))
      (node (ref "M1") (pin "33") (pinfunction "PC4_33") (pintype "bidirectional"))
      (node (ref "U1") (pin "22") (pinfunction "A12_22") (pintype "output"))
      (node (ref "U2") (pin "2") (pinfunction "A12_2") (pintype "input"))
      (node (ref "U3") (pin "2") (pinfunction "A12_2") (pintype "input"))
      (node (ref "X9") (pin "5") (pinfunction "5_5") (pintype "passive"))
    )
    (net (code "15") (name "A13") (class "Default")
      (node (ref "LED14") (pin "A") (pinfunction "A_A") (pintype "passive"))
      (node (ref "M1") (pin "32") (pinfunction "PC5_32") (pintype "bidirectional"))
      (node (ref "U1") (pin "23") (pinfunction "A13_23") (pintype "output"))
      (node (ref "U2") (pin "26") (pinfunction "A13_26") (pintype "input"))
      (node (ref "U3") (pin "26") (pinfunction "A13_26") (pintype "input"))
      (node (ref "X9") (pin "6") (pinfunction "6_6") (pintype "passive"))
    )
    (net (code "16") (name "A14") (class "Default")
      (node (ref "LED15") (pin "A") (pinfunction "A_A") (pintype "passive"))
      (node (ref "M1") (pin "31") (pinfunction "PC6_31") (pintype "bidirectional"))
      (node (ref "SJ1") (pin "1") (pinfunction "1_1") (pintype "passive"))
      (node (ref "U1") (pin "24") (pinfunction "A14_24") (pintype "output"))
      (node (ref "U2") (pin "1") (pinfunction "A14_1") (pintype "input"))
      (node (ref "U3") (pin "1") (pinfunction "A14_1") (pintype "input"))
      (node (ref "U5") (pin "13") (pinfunction "B_13") (pintype "input"))
      (node (ref "X9") (pin "7") (pinfunction "7_7") (pintype "passive"))
    )
    (net (code "17") (name "A15") (class "Default")
      (node (ref "LED16") (pin "A") (pinfunction "A_A") (pintype "passive"))
      (node (ref "M1") (pin "30") (pinfunction "PC7_30") (pintype "bidirectional"))
      (node (ref "U1") (pin "25") (pinfunction "A15_25") (pintype "output"))
      (node (ref "U5") (pin "1") (pinfunction "A_1") (pintype "input"))
      (node (ref "U5") (pin "2") (pinfunction "B_2") (pintype "input"))
      (node (ref "X9") (pin "8") (pinfunction "8_8") (pintype "passive"))
    )
    (net (code "18") (name "BTN1") (class "Default")
      (node (ref "R52") (pin "1") (pinfunction "1_1") (pintype "passive"))
      (node (ref "X12") (pin "8") (pinfunction "8_8") (pintype "passive"))
    )
    (net (code "19") (name "BTN2") (class "Default")
      (node (ref "R50") (pin "1") (pinfunction "1_1") (pintype "passive"))
      (node (ref "X12") (pin "6") (pinfunction "6_6") (pintype "passive"))
    )
    (net (code "20") (name "BTN3") (class "Default")
      (node (ref "R55") (pin "1") (pinfunction "1_1") (pintype "passive"))
      (node (ref "X12") (pin "4") (pinfunction "4_4") (pintype "passive"))
    )
    (net (code "21") (name "BTN4") (class "Default")
      (node (ref "R58") (pin "1") (pinfunction "1_1") (pintype "passive"))
      (node (ref "X12") (pin "2") (pinfunction "2_2") (pintype "passive"))
    )
    (net (code "22") (name "D0") (class "Default")
      (node (ref "LED17") (pin "A") (pinfunction "A_A") (pintype "passive"))
      (node (ref "M1") (pin "22") (pinfunction "PA0_22") (pintype "bidirectional"))
      (node (ref "M2") (pin "7") (pinfunction "D0_7") (pintype "bidirectional"))
      (node (ref "R6") (pin "2") (pinfunction "2_2") (pintype "passive"))
      (node (ref "U2") (pin "11") (pinfunction "D0_11") (pintype "tri_state"))
      (node (ref "U3") (pin "11") (pinfunction "D0_11") (pintype "tri_state"))
      (node (ref "U4") (pin "33") (pinfunction "D0_33") (pintype "bidirectional"))
      (node (ref "X10") (pin "1") (pinfunction "1_1") (pintype "passive"))
    )
    (net (code "23") (name "D1") (class "Default")
      (node (ref "LED18") (pin "A") (pinfunction "A_A") (pintype "passive"))
      (node (ref "M1") (pin "23") (pinfunction "PA1_23") (pintype "bidirectional"))
      (node (ref "M2") (pin "8") (pinfunction "D1_8") (pintype "bidirectional"))
      (node (ref "R7") (pin "2") (pinfunction "2_2") (pintype "passive"))
      (node (ref "U2") (pin "12") (pinfunction "D1_12") (pintype "tri_state"))
      (node (ref "U3") (pin "12") (pinfunction "D1_12") (pintype "tri_state"))
      (node (ref "U4") (pin "32") (pinfunction "D1_32") (pintype "bidirectional"))
      (node (ref "X10") (pin "2") (pinfunction "2_2") (pintype "passive"))
    )
    (net (code "24") (name "D2") (class "Default")
      (node (ref "LED19") (pin "A") (pinfunction "A_A") (pintype "passive"))
      (node (ref "M1") (pin "24") (pinfunction "PA2_24") (pintype "bidirectional"))
      (node (ref "M2") (pin "9") (pinfunction "D2_9") (pintype "bidirectional"))
      (node (ref "R8") (pin "2") (pinfunction "2_2") (pintype "passive"))
      (node (ref "U2") (pin "13") (pinfunction "D2_13") (pintype "tri_state"))
      (node (ref "U3") (pin "13") (pinfunction "D2_13") (pintype "tri_state"))
      (node (ref "U4") (pin "31") (pinfunction "D2_31") (pintype "bidirectional"))
      (node (ref "X10") (pin "3") (pinfunction "3_3") (pintype "passive"))
    )
    (net (code "25") (name "D3") (class "Default")
      (node (ref "LED20") (pin "A") (pinfunction "A_A") (pintype "passive"))
      (node (ref "M1") (pin "25") (pinfunction "PA3_25") (pintype "bidirectional"))
      (node (ref "M2") (pin "10") (pinfunction "D3_10") (pintype "bidirectional"))
      (node (ref "R9") (pin "2") (pinfunction "2_2") (pintype "passive"))
      (node (ref "U2") (pin "15") (pinfunction "D3_15") (pintype "tri_state"))
      (node (ref "U3") (pin "15") (pinfunction "D3_15") (pintype "tri_state"))
      (node (ref "U4") (pin "30") (pinfunction "D3_30") (pintype "bidirectional"))
      (node (ref "X10") (pin "4") (pinfunction "4_4") (pintype "passive"))
    )
    (net (code "26") (name "D4") (class "Default")
      (node (ref "LED21") (pin "A") (pinfunction "A_A") (pintype "passive"))
      (node (ref "M1") (pin "26") (pinfunction "PA4_26") (pintype "bidirectional"))
      (node (ref "M2") (pin "11") (pinfunction "D4_11") (pintype "bidirectional"))
      (node (ref "R10") (pin "2") (pinfunction "2_2") (pintype "passive"))
      (node (ref "U2") (pin "16") (pinfunction "D4_16") (pintype "tri_state"))
      (node (ref "U3") (pin "16") (pinfunction "D4_16") (pintype "tri_state"))
      (node (ref "U4") (pin "29") (pinfunction "D4_29") (pintype "bidirectional"))
      (node (ref "X10") (pin "5") (pinfunction "5_5") (pintype "passive"))
    )
    (net (code "27") (name "D5") (class "Default")
      (node (ref "LED22") (pin "A") (pinfunction "A_A") (pintype "passive"))
      (node (ref "M1") (pin "27") (pinfunction "PA5_27") (pintype "bidirectional"))
      (node (ref "M2") (pin "12") (pinfunction "D5_12") (pintype "bidirectional"))
      (node (ref "R11") (pin "2") (pinfunction "2_2") (pintype "passive"))
      (node (ref "U2") (pin "17") (pinfunction "D5_17") (pintype "tri_state"))
      (node (ref "U3") (pin "17") (pinfunction "D5_17") (pintype "tri_state"))
      (node (ref "U4") (pin "28") (pinfunction "D5_28") (pintype "bidirectional"))
      (node (ref "X10") (pin "6") (pinfunction "6_6") (pintype "passive"))
    )
    (net (code "28") (name "D6") (class "Default")
      (node (ref "LED23") (pin "A") (pinfunction "A_A") (pintype "passive"))
      (node (ref "M1") (pin "28") (pinfunction "PA6_28") (pintype "bidirectional"))
      (node (ref "M2") (pin "13") (pinfunction "D6_13") (pintype "bidirectional"))
      (node (ref "R12") (pin "2") (pinfunction "2_2") (pintype "passive"))
      (node (ref "U2") (pin "18") (pinfunction "D6_18") (pintype "tri_state"))
      (node (ref "U3") (pin "18") (pinfunction "D6_18") (pintype "tri_state"))
      (node (ref "U4") (pin "27") (pinfunction "D6_27") (pintype "bidirectional"))
      (node (ref "X10") (pin "7") (pinfunction "7_7") (pintype "passive"))
    )
    (net (code "29") (name "D7") (class "Default")
      (node (ref "LED24") (pin "A") (pinfunction "A_A") (pintype "passive"))
      (node (ref "M1") (pin "29") (pinfunction "PA7_29") (pintype "bidirectional"))
      (node (ref "M2") (pin "14") (pinfunction "D7_14") (pintype "bidirectional"))
      (node (ref "R13") (pin "2") (pinfunction "2_2") (pintype "passive"))
      (node (ref "U2") (pin "19") (pinfunction "D7_19") (pintype "tri_state"))
      (node (ref "U3") (pin "19") (pinfunction "D7_19") (pintype "tri_state"))
      (node (ref "U4") (pin "26") (pinfunction "D7_26") (pintype "bidirectional"))
      (node (ref "X10") (pin "8") (pinfunction "8_8") (pintype "passive"))
    )
    (net (code "30") (name "EEPROM_~{CS}") (class "Default")
      (node (ref "LED28") (pin "C") (pinfunction "C_C") (pintype "passive"))
      (node (ref "SJ2") (pin "2") (pinfunction "2_2") (pintype "passive"))
      (node (ref "U2") (pin "20") (pinfunction "~{CE}_20") (pintype "input"))
    )
    (net (code "31") (name "EEPROM_~{OE}") (class "Default")
      (node (ref "M1") (pin "38") (pinfunction "PD7_38") (pintype "bidirectional"))
      (node (ref "U2") (pin "22") (pinfunction "~{OE}_22") (pintype "input"))
    )
    (net (code "32") (name "EEPROM_~{WE}") (class "Default")
      (node (ref "M1") (pin "39") (pinfunction "PG2_39") (pintype "bidirectional"))
      (node (ref "U2") (pin "27") (pinfunction "~{WE}_27") (pintype "input"))
    )
    (net (code "33") (name "GND") (class "Default")
      (node (ref "C1") (pin "2") (pinfunction "2_2") (pintype "passive"))
      (node (ref "C2") (pin "2") (pinfunction "2_2") (pintype "passive"))
      (node (ref "C3") (pin "2") (pinfunction "2_2") (pintype "passive"))
      (node (ref "C4") (pin "2") (pinfunction "2_2") (pintype "passive"))
      (node (ref "C5") (pin "2") (pinfunction "2_2") (pintype "passive"))
      (node (ref "C6") (pin "2") (pinfunction "2_2") (pintype "passive"))
      (node (ref "C7") (pin "2") (pinfunction "2_2") (pintype "passive"))
      (node (ref "C8") (pin "2") (pinfunction "2_2") (pintype "passive"))
      (node (ref "JP6") (pin "1") (pinfunction "1_1") (pintype "passive"))
      (node (ref "M1") (pin "GND@2") (pinfunction "GND_GND@2") (pintype "bidirectional"))
      (node (ref "M1") (pin "GND@3") (pinfunction "GND_GND@3") (pintype "bidirectional"))
      (node (ref "M2") (pin "1") (pinfunction "VSS_1") (pintype "power_in"))
      (node (ref "M2") (pin "16") (pinfunction "K_16") (pintype "power_in"))
      (node (ref "R17") (pin "2") (pinfunction "2_2") (pintype "passive"))
      (node (ref "R19") (pin "2") (pinfunction "2_2") (pintype "passive"))
      (node (ref "R20") (pin "2") (pinfunction "2_2") (pintype "passive"))
      (node (ref "R21") (pin "2") (pinfunction "2_2") (pintype "passive"))
      (node (ref "R22") (pin "2") (pinfunction "2_2") (pintype "passive"))
      (node (ref "R23") (pin "2") (pinfunction "2_2") (pintype "passive"))
      (node (ref "R24") (pin "2") (pinfunction "2_2") (pintype "passive"))
      (node (ref "R25") (pin "2") (pinfunction "2_2") (pintype "passive"))
      (node (ref "R26") (pin "2") (pinfunction "2_2") (pintype "passive"))
      (node (ref "R27") (pin "2") (pinfunction "2_2") (pintype "passive"))
      (node (ref "R28") (pin "2") (pinfunction "2_2") (pintype "passive"))
      (node (ref "R29") (pin "2") (pinfunction "2_2") (pintype "passive"))
      (node (ref "R30") (pin "2") (pinfunction "2_2") (pintype "passive"))
      (node (ref "R31") (pin "2") (pinfunction "2_2") (pintype "passive"))
      (node (ref "R32") (pin "2") (pinfunction "2_2") (pintype "passive"))
      (node (ref "R33") (pin "2") (pinfunction "2_2") (pintype "passive"))
      (node (ref "R34") (pin "2") (pinfunction "2_2") (pintype "passive"))
      (node (ref "R35") (pin "2") (pinfunction "2_2") (pintype "passive"))
      (node (ref "R36") (pin "2") (pinfunction "2_2") (pintype "passive"))
      (node (ref "R37") (pin "2") (pinfunction "2_2") (pintype "passive"))
      (node (ref "R38") (pin "2") (pinfunction "2_2") (pintype "passive"))
      (node (ref "R39") (pin "2") (pinfunction "2_2") (pintype "passive"))
      (node (ref "R40") (pin "2") (pinfunction "2_2") (pintype "passive"))
      (node (ref "R41") (pin "2") (pinfunction "2_2") (pintype "passive"))
      (node (ref "R42") (pin "2") (pinfunction "2_2") (pintype "passive"))
      (node (ref "R43") (pin "2") (pinfunction "2_2") (pintype "passive"))
      (node (ref "R44") (pin "2") (pinfunction "2_2") (pintype "passive"))
      (node (ref "R45") (pin "2") (pinfunction "2_2") (pintype "passive"))
      (node (ref "R46") (pin "2") (pinfunction "2_2") (pintype "passive"))
      (node (ref "R51") (pin "2") (pinfunction "2_2") (pintype "passive"))
      (node (ref "R53") (pin "2") (pinfunction "2_2") (pintype "passive"))
      (node (ref "R56") (pin "2") (pinfunction "2_2") (pintype "passive"))
      (node (ref "R59") (pin "2") (pinfunction "2_2") (pintype "passive"))
      (node (ref "R60") (pin "2") (pinfunction "2_2") (pintype "passive"))
      (node (ref "R61") (pin "1") (pinfunction "1_1") (pintype "passive"))
      (node (ref "SJ7") (pin "1") (pinfunction "1_1") (pintype "passive"))
      (node (ref "U1") (pin "21") (pinfunction "VSS_21") (pintype "power_in"))
      (node (ref "U2") (pin "14") (pinfunction "GND_14") (pintype "power_in"))
      (node (ref "U3") (pin "14") (pinfunction "GND_14") (pintype "power_in"))
      (node (ref "U4") (pin "1") (pinfunction "VSS_1") (pintype "power_in"))
      (node (ref "U5") (pin "7") (pinfunction "-UB_7") (pintype "power_in"))
      (node (ref "U6") (pin "8") (pinfunction "-UB_8") (pintype "power_in"))
      (node (ref "U7") (pin "7") (pinfunction "-UB_7") (pintype "power_in"))
      (node (ref "X11") (pin "1") (pinfunction "1_1") (pintype "passive"))
      (node (ref "X13") (pin "3") (pinfunction "3_3") (pintype "passive"))
      (node (ref "X13") (pin "4") (pinfunction "4_4") (pintype "passive"))
      (node (ref "X14") (pin "3") (pinfunction "3_3") (pintype "passive"))
      (node (ref "X14") (pin "4") (pinfunction "4_4") (pintype "passive"))
      (node (ref "X15") (pin "3") (pinfunction "3_3") (pintype "passive"))
      (node (ref "X15") (pin "4") (pinfunction "4_4") (pintype "passive"))
      (node (ref "X16") (pin "3") (pinfunction "3_3") (pintype "passive"))
      (node (ref "X16") (pin "4") (pinfunction "4_4") (pintype "passive"))
      (node (ref "X5") (pin "7") (pinfunction "7_7") (pintype "passive"))
      (node (ref "X5") (pin "8") (pinfunction "8_8") (pintype "passive"))
      (node (ref "X6") (pin "3") (pinfunction "3_3") (pintype "passive"))
      (node (ref "X6") (pin "4") (pinfunction "4_4") (pintype "passive"))
      (node (ref "X7") (pin "3") (pinfunction "3_3") (pintype "passive"))
      (node (ref "X7") (pin "4") (pinfunction "4_4") (pintype "passive"))
      (node (ref "X8") (pin "9") (pinfunction "9_9") (pintype "passive"))
    )
    (net (code "34") (name "HALT_BTN") (class "Default")
      (node (ref "M1") (pin "40") (pinfunction "PG1_40") (pintype "bidirectional"))
      (node (ref "X7") (pin "1") (pinfunction "1_1") (pintype "passive"))
      (node (ref "X7") (pin "2") (pinfunction "2_2") (pintype "passive"))
    )
    (net (code "35") (name "HALT_LED") (class "Default")
      (node (ref "LED34") (pin "A") (pinfunction "A_A") (pintype "passive"))
      (node (ref "M1") (pin "41") (pinfunction "PG0_41") (pintype "bidirectional"))
    )
    (net (code "36") (name "IRQB") (class "Default")
      (node (ref "JP3") (pin "2") (pinfunction "2_2") (pintype "passive"))
      (node (ref "LED27") (pin "C") (pinfunction "C_C") (pintype "passive"))
      (node (ref "M1") (pin "A13") (pinfunction "PK5_A13") (pintype "bidirectional"))
      (node (ref "R2") (pin "2") (pinfunction "2_2") (pintype "passive"))
      (node (ref "U1") (pin "4") (pinfunction "~{IRQB}_4") (pintype "input"))
      (node (ref "X5") (pin "2") (pinfunction "2_2") (pintype "passive"))
    )
    (net (code "37") (name "LCD_CS") (class "Default")
      (node (ref "LED31") (pin "A") (pinfunction "A_A") (pintype "passive"))
      (node (ref "M2") (pin "6") (pinfunction "E_6") (pintype "input"))
      (node (ref "SJ7") (pin "2") (pinfunction "2_2") (pintype "passive"))
    )
    (net (code "38") (name "NMIB") (class "Default")
      (node (ref "M1") (pin "A14") (pinfunction "PK6_A14") (pintype "bidirectional"))
      (node (ref "R3") (pin "2") (pinfunction "2_2") (pintype "passive"))
      (node (ref "U1") (pin "6") (pinfunction "~{NMIB}_6") (pintype "input"))
    )
    (net (code "39") (name "Net-(LED1-PadC)") (class "Default")
      (node (ref "LED1") (pin "C") (pinfunction "C_C") (pintype "passive"))
      (node (ref "R21") (pin "1") (pinfunction "1_1") (pintype "passive"))
    )
    (net (code "40") (name "Net-(LED2-PadC)") (class "Default")
      (node (ref "LED2") (pin "C") (pinfunction "C_C") (pintype "passive"))
      (node (ref "R22") (pin "1") (pinfunction "1_1") (pintype "passive"))
    )
    (net (code "41") (name "Net-(LED3-PadC)") (class "Default")
      (node (ref "LED3") (pin "C") (pinfunction "C_C") (pintype "passive"))
      (node (ref "R23") (pin "1") (pinfunction "1_1") (pintype "passive"))
    )
    (net (code "42") (name "Net-(LED4-PadC)") (class "Default")
      (node (ref "LED4") (pin "C") (pinfunction "C_C") (pintype "passive"))
      (node (ref "R24") (pin "1") (pinfunction "1_1") (pintype "passive"))
    )
    (net (code "43") (name "Net-(LED5-PadC)") (class "Default")
      (node (ref "LED5") (pin "C") (pinfunction "C_C") (pintype "passive"))
      (node (ref "R25") (pin "1") (pinfunction "1_1") (pintype "passive"))
    )
    (net (code "44") (name "Net-(LED6-PadC)") (class "Default")
      (node (ref "LED6") (pin "C") (pinfunction "C_C") (pintype "passive"))
      (node (ref "R26") (pin "1") (pinfunction "1_1") (pintype "passive"))
    )
    (net (code "45") (name "Net-(LED7-PadC)") (class "Default")
      (node (ref "LED7") (pin "C") (pinfunction "C_C") (pintype "passive"))
      (node (ref "R27") (pin "1") (pinfunction "1_1") (pintype "passive"))
    )
    (net (code "46") (name "Net-(LED8-PadC)") (class "Default")
      (node (ref "LED8") (pin "C") (pinfunction "C_C") (pintype "passive"))
      (node (ref "R28") (pin "1") (pinfunction "1_1") (pintype "passive"))
    )
    (net (code "47") (name "Net-(LED9-PadC)") (class "Default")
      (node (ref "LED9") (pin "C") (pinfunction "C_C") (pintype "passive"))
      (node (ref "R29") (pin "1") (pinfunction "1_1") (pintype "passive"))
    )
    (net (code "48") (name "Net-(LED10-PadC)") (class "Default")
      (node (ref "LED10") (pin "C") (pinfunction "C_C") (pintype "passive"))
      (node (ref "R30") (pin "1") (pinfunction "1_1") (pintype "passive"))
    )
    (net (code "49") (name "Net-(LED11-PadC)") (class "Default")
      (node (ref "LED11") (pin "C") (pinfunction "C_C") (pintype "passive"))
      (node (ref "R31") (pin "1") (pinfunction "1_1") (pintype "passive"))
    )
    (net (code "50") (name "Net-(LED12-PadC)") (class "Default")
      (node (ref "LED12") (pin "C") (pinfunction "C_C") (pintype "passive"))
      (node (ref "R32") (pin "1") (pinfunction "1_1") (pintype "passive"))
    )
    (net (code "51") (name "Net-(LED13-PadC)") (class "Default")
      (node (ref "LED13") (pin "C") (pinfunction "C_C") (pintype "passive"))
      (node (ref "R33") (pin "1") (pinfunction "1_1") (pintype "passive"))
    )
    (net (code "52") (name "Net-(LED14-PadC)") (class "Default")
      (node (ref "LED14") (pin "C") (pinfunction "C_C") (pintype "passive"))
      (node (ref "R34") (pin "1") (pinfunction "1_1") (pintype "passive"))
    )
    (net (code "53") (name "Net-(LED15-PadC)") (class "Default")
      (node (ref "LED15") (pin "C") (pinfunction "C_C") (pintype "passive"))
      (node (ref "R35") (pin "1") (pinfunction "1_1") (pintype "passive"))
    )
    (net (code "54") (name "Net-(LED16-PadC)") (class "Default")
      (node (ref "LED16") (pin "C") (pinfunction "C_C") (pintype "passive"))
      (node (ref "R36") (pin "1") (pinfunction "1_1") (pintype "passive"))
    )
    (net (code "55") (name "Net-(LED17-PadC)") (class "Default")
      (node (ref "LED17") (pin "C") (pinfunction "C_C") (pintype "passive"))
      (node (ref "R37") (pin "1") (pinfunction "1_1") (pintype "passive"))
    )
    (net (code "56") (name "Net-(LED18-PadC)") (class "Default")
      (node (ref "LED18") (pin "C") (pinfunction "C_C") (pintype "passive"))
      (node (ref "R38") (pin "1") (pinfunction "1_1") (pintype "passive"))
    )
    (net (code "57") (name "Net-(LED19-PadC)") (class "Default")
      (node (ref "LED19") (pin "C") (pinfunction "C_C") (pintype "passive"))
      (node (ref "R39") (pin "1") (pinfunction "1_1") (pintype "passive"))
    )
    (net (code "58") (name "Net-(LED20-PadC)") (class "Default")
      (node (ref "LED20") (pin "C") (pinfunction "C_C") (pintype "passive"))
      (node (ref "R40") (pin "1") (pinfunction "1_1") (pintype "passive"))
    )
    (net (code "59") (name "Net-(LED21-PadC)") (class "Default")
      (node (ref "LED21") (pin "C") (pinfunction "C_C") (pintype "passive"))
      (node (ref "R41") (pin "1") (pinfunction "1_1") (pintype "passive"))
    )
    (net (code "60") (name "Net-(LED22-PadC)") (class "Default")
      (node (ref "LED22") (pin "C") (pinfunction "C_C") (pintype "passive"))
      (node (ref "R42") (pin "1") (pinfunction "1_1") (pintype "passive"))
    )
    (net (code "61") (name "Net-(LED23-PadC)") (class "Default")
      (node (ref "LED23") (pin "C") (pinfunction "C_C") (pintype "passive"))
      (node (ref "R43") (pin "1") (pinfunction "1_1") (pintype "passive"))
    )
    (net (code "62") (name "Net-(LED24-PadC)") (class "Default")
      (node (ref "LED24") (pin "C") (pinfunction "C_C") (pintype "passive"))
      (node (ref "R44") (pin "1") (pinfunction "1_1") (pintype "passive"))
    )
    (net (code "63") (name "Net-(LED25-PadC)") (class "Default")
      (node (ref "LED25") (pin "C") (pinfunction "C_C") (pintype "passive"))
      (node (ref "R45") (pin "1") (pinfunction "1_1") (pintype "passive"))
    )
    (net (code "64") (name "Net-(LED26-PadC)") (class "Default")
      (node (ref "LED26") (pin "C") (pinfunction "C_C") (pintype "passive"))
      (node (ref "R46") (pin "1") (pinfunction "1_1") (pintype "passive"))
    )
    (net (code "65") (name "Net-(LED27-PadA)") (class "Default")
      (node (ref "LED27") (pin "A") (pinfunction "A_A") (pintype "passive"))
      (node (ref "R47") (pin "1") (pinfunction "1_1") (pintype "passive"))
    )
    (net (code "66") (name "Net-(LED28-PadA)") (class "Default")
      (node (ref "LED28") (pin "A") (pinfunction "A_A") (pintype "passive"))
      (node (ref "R14") (pin "1") (pinfunction "1_1") (pintype "passive"))
    )
    (net (code "67") (name "Net-(LED29-PadA)") (class "Default")
      (node (ref "LED29") (pin "A") (pinfunction "A_A") (pintype "passive"))
      (node (ref "R15") (pin "1") (pinfunction "1_1") (pintype "passive"))
    )
    (net (code "68") (name "Net-(LED30-PadA)") (class "Default")
      (node (ref "LED30") (pin "A") (pinfunction "A_A") (pintype "passive"))
      (node (ref "R16") (pin "1") (pinfunction "1_1") (pintype "passive"))
    )
    (net (code "69") (name "Net-(LED31-PadC)") (class "Default")
      (node (ref "LED31") (pin "C") (pinfunction "C_C") (pintype "passive"))
      (node (ref "R17") (pin "1") (pinfunction "1_1") (pintype "passive"))
    )
    (net (code "70") (name "Net-(LED32-PadA)") (class "Default")
      (node (ref "LED32") (pin "A") (pinfunction "A_A") (pintype "passive"))
      (node (ref "R18") (pin "1") (pinfunction "1_1") (pintype "passive"))
    )
    (net (code "71") (name "Net-(LED33-PadC)") (class "Default")
      (node (ref "LED33") (pin "C") (pinfunction "C_C") (pintype "passive"))
      (node (ref "R19") (pin "1") (pinfunction "1_1") (pintype "passive"))
    )
    (net (code "72") (name "Net-(LED34-PadC)") (class "Default")
      (node (ref "LED34") (pin "C") (pinfunction "C_C") (pintype "passive"))
      (node (ref "R20") (pin "1") (pinfunction "1_1") (pintype "passive"))
    )
    (net (code "73") (name "Net-(LED35-PadC)") (class "Default")
      (node (ref "LED35") (pin "C") (pinfunction "C_C") (pintype "passive"))
      (node (ref "R53") (pin "1") (pinfunction "1_1") (pintype "passive"))
    )
    (net (code "74") (name "Net-(LED36-PadC)") (class "Default")
      (node (ref "LED36") (pin "C") (pinfunction "C_C") (pintype "passive"))
      (node (ref "R51") (pin "1") (pinfunction "1_1") (pintype "passive"))
    )
    (net (code "75") (name "Net-(LED37-PadC)") (class "Default")
      (node (ref "LED37") (pin "C") (pinfunction "C_C") (pintype "passive"))
      (node (ref "R56") (pin "1") (pinfunction "1_1") (pintype "passive"))
    )
    (net (code "76") (name "Net-(LED38-PadC)") (class "Default")
      (node (ref "LED38") (pin "C") (pinfunction "C_C") (pintype "passive"))
      (node (ref "R59") (pin "1") (pinfunction "1_1") (pintype "passive"))
    )
    (net (code "77") (name "Net-(LED39-PadC)") (class "Default")
      (node (ref "LED39") (pin "C") (pinfunction "C_C") (pintype "passive"))
      (node (ref "R60") (pin "1") (pinfunction "1_1") (pintype "passive"))
    )
    (net (code "78") (name "Net-(M2-VO)") (class "Default")
      (node (ref "M2") (pin "3") (pinfunction "VO_3") (pintype "bidirectional"))
      (node (ref "R61") (pin "2") (pinfunction "2_2") (pintype "passive"))
    )
    (net (code "79") (name "Net-(R48-Pad2)") (class "Default")
      (node (ref "R48") (pin "2") (pinfunction "2_2") (pintype "passive"))
      (node (ref "R52") (pin "2") (pinfunction "2_2") (pintype "passive"))
      (node (ref "X13") (pin "1") (pinfunction "1_1") (pintype "passive"))
      (node (ref "X13") (pin "2") (pinfunction "2_2") (pintype "passive"))
    )
    (net (code "80") (name "Net-(R49-Pad2)") (class "Default")
      (node (ref "R49") (pin "2") (pinfunction "2_2") (pintype "passive"))
      (node (ref "R50") (pin "2") (pinfunction "2_2") (pintype "passive"))
      (node (ref "X14") (pin "1") (pinfunction "1_1") (pintype "passive"))
      (node (ref "X14") (pin "2") (pinfunction "2_2") (pintype "passive"))
    )
    (net (code "81") (name "Net-(R54-Pad2)") (class "Default")
      (node (ref "R54") (pin "2") (pinfunction "2_2") (pintype "passive"))
      (node (ref "R55") (pin "2") (pinfunction "2_2") (pintype "passive"))
      (node (ref "X15") (pin "1") (pinfunction "1_1") (pintype "passive"))
      (node (ref "X15") (pin "2") (pinfunction "2_2") (pintype "passive"))
    )
    (net (code "82") (name "Net-(R57-Pad2)") (class "Default")
      (node (ref "R57") (pin "2") (pinfunction "2_2") (pintype "passive"))
      (node (ref "R58") (pin "2") (pinfunction "2_2") (pintype "passive"))
      (node (ref "X16") (pin "1") (pinfunction "1_1") (pintype "passive"))
      (node (ref "X16") (pin "2") (pinfunction "2_2") (pintype "passive"))
    )
    (net (code "83") (name "Net-(U1A-BE)") (class "Default")
      (node (ref "JP2") (pin "2") (pinfunction "2_2") (pintype "passive"))
      (node (ref "R5") (pin "2") (pinfunction "2_2") (pintype "passive"))
      (node (ref "U1") (pin "36") (pinfunction "BE_36") (pintype "input"))
    )
    (net (code "84") (name "Net-(U1A-D0)") (class "Default")
      (node (ref "R6") (pin "1") (pinfunction "1_1") (pintype "passive"))
      (node (ref "U1") (pin "33") (pinfunction "D0_33") (pintype "bidirectional"))
    )
    (net (code "85") (name "Net-(U1A-D1)") (class "Default")
      (node (ref "R7") (pin "1") (pinfunction "1_1") (pintype "passive"))
      (node (ref "U1") (pin "32") (pinfunction "D1_32") (pintype "bidirectional"))
    )
    (net (code "86") (name "Net-(U1A-D2)") (class "Default")
      (node (ref "R8") (pin "1") (pinfunction "1_1") (pintype "passive"))
      (node (ref "U1") (pin "31") (pinfunction "D2_31") (pintype "bidirectional"))
    )
    (net (code "87") (name "Net-(U1A-D3)") (class "Default")
      (node (ref "R9") (pin "1") (pinfunction "1_1") (pintype "passive"))
      (node (ref "U1") (pin "30") (pinfunction "D3_30") (pintype "bidirectional"))
    )
    (net (code "88") (name "Net-(U1A-D4)") (class "Default")
      (node (ref "R10") (pin "1") (pinfunction "1_1") (pintype "passive"))
      (node (ref "U1") (pin "29") (pinfunction "D4_29") (pintype "bidirectional"))
    )
    (net (code "89") (name "Net-(U1A-D5)") (class "Default")
      (node (ref "R11") (pin "1") (pinfunction "1_1") (pintype "passive"))
      (node (ref "U1") (pin "28") (pinfunction "D5_28") (pintype "bidirectional"))
    )
    (net (code "90") (name "Net-(U1A-D6)") (class "Default")
      (node (ref "R12") (pin "1") (pinfunction "1_1") (pintype "passive"))
      (node (ref "U1") (pin "27") (pinfunction "D6_27") (pintype "bidirectional"))
    )
    (net (code "91") (name "Net-(U1A-D7)") (class "Default")
      (node (ref "R13") (pin "1") (pinfunction "1_1") (pintype "passive"))
      (node (ref "U1") (pin "26") (pinfunction "D7_26") (pintype "bidirectional"))
    )
    (net (code "92") (name "Net-(U1A-RDY)") (class "Default")
      (node (ref "JP1") (pin "2") (pinfunction "2_2") (pintype "passive"))
      (node (ref "R1") (pin "2") (pinfunction "2_2") (pintype "passive"))
      (node (ref "U1") (pin "2") (pinfunction "RDY_2") (pintype "input"))
    )
    (net (code "93") (name "Net-(U3-~{OE})") (class "Default")
      (node (ref "SJ1") (pin "2") (pinfunction "2_2") (pintype "passive"))
      (node (ref "U3") (pin "22") (pinfunction "~{OE}_22") (pintype "input"))
    )
    (net (code "94") (name "Net-(U4A-CS1)") (class "Default")
      (node (ref "JP7") (pin "1") (pinfunction "1_1") (pintype "passive"))
      (node (ref "U4") (pin "24") (pinfunction "CS1_24") (pintype "input"))
    )
    (net (code "95") (name "Net-(U4A-PA0)") (class "Default")
      (node (ref "U4") (pin "2") (pinfunction "PA0_2") (pintype "bidirectional"))
      (node (ref "X11") (pin "2") (pinfunction "2_2") (pintype "passive"))
    )
    (net (code "96") (name "Net-(U4A-PA1)") (class "Default")
      (node (ref "U4") (pin "3") (pinfunction "PA1_3") (pintype "bidirectional"))
      (node (ref "X11") (pin "3") (pinfunction "3_3") (pintype "passive"))
    )
    (net (code "97") (name "Net-(U4A-PA2)") (class "Default")
      (node (ref "U4") (pin "4") (pinfunction "PA2_4") (pintype "bidirectional"))
      (node (ref "X11") (pin "4") (pinfunction "4_4") (pintype "passive"))
    )
    (net (code "98") (name "Net-(U4A-PA3)") (class "Default")
      (node (ref "U4") (pin "5") (pinfunction "PA3_5") (pintype "bidirectional"))
      (node (ref "X11") (pin "5") (pinfunction "5_5") (pintype "passive"))
    )
    (net (code "99") (name "Net-(U4A-PA4)") (class "Default")
      (node (ref "U4") (pin "6") (pinfunction "PA4_6") (pintype "bidirectional"))
      (node (ref "X11") (pin "6") (pinfunction "6_6") (pintype "passive"))
    )
    (net (code "100") (name "Net-(U4A-PA5)") (class "Default")
      (node (ref "U4") (pin "7") (pinfunction "PA5_7") (pintype "bidirectional"))
      (node (ref "X11") (pin "7") (pinfunction "7_7") (pintype "passive"))
    )
    (net (code "101") (name "Net-(U4A-PA6)") (class "Default")
      (node (ref "U4") (pin "8") (pinfunction "PA6_8") (pintype "bidirectional"))
      (node (ref "X11") (pin "8") (pinfunction "8_8") (pintype "passive"))
    )
    (net (code "102") (name "Net-(U4A-PA7)") (class "Default")
      (node (ref "U4") (pin "9") (pinfunction "PA7_9") (pintype "bidirectional"))
      (node (ref "X11") (pin "9") (pinfunction "9_9") (pintype "passive"))
    )
    (net (code "103") (name "Net-(U4A-PB0)") (class "Default")
      (node (ref "U4") (pin "10") (pinfunction "PB0_10") (pintype "bidirectional"))
      (node (ref "X8") (pin "1") (pinfunction "1_1") (pintype "passive"))
    )
    (net (code "104") (name "Net-(U4A-PB1)") (class "Default")
      (node (ref "U4") (pin "11") (pinfunction "PB1_11") (pintype "bidirectional"))
      (node (ref "X8") (pin "2") (pinfunction "2_2") (pintype "passive"))
    )
    (net (code "105") (name "Net-(U4A-PB2)") (class "Default")
      (node (ref "U4") (pin "12") (pinfunction "PB2_12") (pintype "bidirectional"))
      (node (ref "X8") (pin "3") (pinfunction "3_3") (pintype "passive"))
    )
    (net (code "106") (name "Net-(U4A-PB3)") (class "Default")
      (node (ref "U4") (pin "13") (pinfunction "PB3_13") (pintype "bidirectional"))
      (node (ref "X8") (pin "4") (pinfunction "4_4") (pintype "passive"))
    )
    (net (code "107") (name "Net-(U4A-PB4)") (class "Default")
      (node (ref "U4") (pin "14") (pinfunction "PB4_14") (pintype "bidirectional"))
      (node (ref "X8") (pin "5") (pinfunction "5_5") (pintype "passive"))
    )
    (net (code "108") (name "Net-(U4A-PB5)") (class "Default")
      (node (ref "U4") (pin "15") (pinfunction "PB5_15") (pintype "bidirectional"))
      (node (ref "X8") (pin "6") (pinfunction "6_6") (pintype "passive"))
    )
    (net (code "109") (name "Net-(U4A-PB6)") (class "Default")
      (node (ref "U4") (pin "16") (pinfunction "PB6_16") (pintype "bidirectional"))
      (node (ref "X8") (pin "7") (pinfunction "7_7") (pintype "passive"))
    )
    (net (code "110") (name "Net-(U4A-PB7)") (class "Default")
      (node (ref "U4") (pin "17") (pinfunction "PB7_17") (pintype "bidirectional"))
      (node (ref "X8") (pin "8") (pinfunction "8_8") (pintype "passive"))
    )
    (net (code "111") (name "Net-(U4A-~{IRQB})") (class "Default")
      (node (ref "JP3") (pin "1") (pinfunction "1_1") (pintype "passive"))
      (node (ref "U4") (pin "21") (pinfunction "~{IRQB}_21") (pintype "output"))
    )
    (net (code "112") (name "Net-(U5C-Y)") (class "Default")
      (node (ref "SJ2") (pin "3") (pinfunction "3_3") (pintype "passive"))
      (node (ref "U5") (pin "12") (pinfunction "A_12") (pintype "input"))
      (node (ref "U5") (pin "3") (pinfunction "Y_3") (pintype "output"))
      (node (ref "U5") (pin "4") (pinfunction "A_4") (pintype "input"))
    )
    (net (code "113") (name "Net-(U5D-Y)") (class "Default")
      (node (ref "SJ4") (pin "3") (pinfunction "3_3") (pintype "passive"))
      (node (ref "U5") (pin "6") (pinfunction "Y_6") (pintype "output"))
    )
    (net (code "114") (name "Net-(U5E-A)") (class "Default")
      (node (ref "U5") (pin "9") (pinfunction "A_9") (pintype "input"))
      (node (ref "X17") (pin "2") (pinfunction "2_2") (pintype "passive"))
    )
    (net (code "115") (name "Net-(U5E-B)") (class "Default")
      (node (ref "U5") (pin "10") (pinfunction "B_10") (pintype "input"))
      (node (ref "X17") (pin "1") (pinfunction "1_1") (pintype "passive"))
    )
    (net (code "116") (name "Net-(U5E-Y)") (class "Default")
      (node (ref "U5") (pin "8") (pinfunction "Y_8") (pintype "output"))
      (node (ref "X17") (pin "3") (pinfunction "3_3") (pintype "passive"))
    )
    (net (code "117") (name "Net-(U5F-Y)") (class "Default")
      (node (ref "JP5") (pin "1") (pinfunction "1_1") (pintype "passive"))
      (node (ref "U5") (pin "11") (pinfunction "Y_11") (pintype "output"))
    )
    (net (code "118") (name "Net-(U6C-G1)") (class "Default")
      (node (ref "JP4") (pin "2") (pinfunction "2_2") (pintype "passive"))
      (node (ref "U6") (pin "6") (pinfunction "G1_6") (pintype "input"))
    )
    (net (code "119") (name "Net-(U6C-Y0)") (class "Default")
      (node (ref "SJ3") (pin "3") (pinfunction "3_3") (pintype "passive"))
      (node (ref "U6") (pin "15") (pinfunction "Y0_15") (pintype "output"))
      (node (ref "X3") (pin "1") (pinfunction "1_1") (pintype "passive"))
    )
    (net (code "120") (name "Net-(U6C-Y1)") (class "Default")
      (node (ref "U6") (pin "14") (pinfunction "Y1_14") (pintype "output"))
      (node (ref "U7") (pin "1") (pinfunction "A_1") (pintype "input"))
      (node (ref "U7") (pin "2") (pinfunction "B_2") (pintype "input"))
      (node (ref "X3") (pin "2") (pinfunction "2_2") (pintype "passive"))
    )
    (net (code "121") (name "Net-(U6C-Y2)") (class "Default")
      (node (ref "U6") (pin "13") (pinfunction "Y2_13") (pintype "output"))
      (node (ref "X3") (pin "3") (pinfunction "3_3") (pintype "passive"))
    )
    (net (code "122") (name "Net-(U6C-Y3)") (class "Default")
      (node (ref "U6") (pin "12") (pinfunction "Y3_12") (pintype "output"))
      (node (ref "X3") (pin "4") (pinfunction "4_4") (pintype "passive"))
    )
    (net (code "123") (name "Net-(U6C-Y4)") (class "Default")
      (node (ref "U6") (pin "11") (pinfunction "Y4_11") (pintype "output"))
      (node (ref "X3") (pin "5") (pinfunction "5_5") (pintype "passive"))
    )
    (net (code "124") (name "Net-(U6C-Y5)") (class "Default")
      (node (ref "U6") (pin "10") (pinfunction "Y5_10") (pintype "output"))
      (node (ref "X3") (pin "6") (pinfunction "6_6") (pintype "passive"))
    )
    (net (code "125") (name "Net-(U6C-Y6)") (class "Default")
      (node (ref "U6") (pin "9") (pinfunction "Y6_9") (pintype "output"))
      (node (ref "X3") (pin "7") (pinfunction "7_7") (pintype "passive"))
    )
    (net (code "126") (name "Net-(U6C-~{G2A})") (class "Default")
      (node (ref "JP5") (pin "2") (pinfunction "2_2") (pintype "passive"))
      (node (ref "U6") (pin "4") (pinfunction "~{G2A}_4") (pintype "input"))
    )
    (net (code "127") (name "Net-(U6C-~{G2B})") (class "Default")
      (node (ref "JP6") (pin "2") (pinfunction "2_2") (pintype "passive"))
      (node (ref "U6") (pin "5") (pinfunction "~{G2B}_5") (pintype "input"))
    )
    (net (code "128") (name "Net-(U7C-Y)") (class "Default")
      (node (ref "U7") (pin "3") (pinfunction "Y_3") (pintype "output"))
      (node (ref "U7") (pin "4") (pinfunction "A_4") (pintype "input"))
    )
    (net (code "129") (name "Net-(U7D-Y)") (class "Default")
      (node (ref "U7") (pin "10") (pinfunction "B_10") (pintype "input"))
      (node (ref "U7") (pin "6") (pinfunction "Y_6") (pintype "output"))
      (node (ref "U7") (pin "9") (pinfunction "A_9") (pintype "input"))
    )
    (net (code "130") (name "Net-(U7E-Y)") (class "Default")
      (node (ref "SJ7") (pin "3") (pinfunction "3_3") (pintype "passive"))
      (node (ref "U7") (pin "8") (pinfunction "Y_8") (pintype "output"))
    )
    (net (code "131") (name "Net-(U7F-A)") (class "Default")
      (node (ref "U7") (pin "12") (pinfunction "A_12") (pintype "input"))
      (node (ref "X4") (pin "2") (pinfunction "2_2") (pintype "passive"))
    )
    (net (code "132") (name "Net-(U7F-B)") (class "Default")
      (node (ref "U7") (pin "13") (pinfunction "B_13") (pintype "input"))
      (node (ref "X4") (pin "3") (pinfunction "3_3") (pintype "passive"))
    )
    (net (code "133") (name "Net-(U7F-Y)") (class "Default")
      (node (ref "U7") (pin "11") (pinfunction "Y_11") (pintype "output"))
      (node (ref "X4") (pin "1") (pinfunction "1_1") (pintype "passive"))
    )
    (net (code "134") (name "PHI2") (class "Default")
      (node (ref "LED33") (pin "A") (pinfunction "A_A") (pintype "passive"))
      (node (ref "M1") (pin "A11") (pinfunction "PK3_A11") (pintype "bidirectional"))
      (node (ref "U1") (pin "37") (pinfunction "PHI2_37") (pintype "input"))
      (node (ref "U4") (pin "25") (pinfunction "PHI2_25") (pintype "input"))
      (node (ref "U5") (pin "5") (pinfunction "B_5") (pintype "input"))
      (node (ref "U7") (pin "5") (pinfunction "B_5") (pintype "input"))
      (node (ref "X5") (pin "4") (pinfunction "4_4") (pintype "passive"))
    )
    (net (code "135") (name "PIA_~{CS}") (class "Default")
      (node (ref "LED30") (pin "C") (pinfunction "C_C") (pintype "passive"))
      (node (ref "SJ3") (pin "2") (pinfunction "2_2") (pintype "passive"))
      (node (ref "U4") (pin "23") (pinfunction "~{CS2B}_23") (pintype "input"))
    )
    (net (code "136") (name "RAM_~{CS}") (class "Default")
      (node (ref "LED29") (pin "C") (pinfunction "C_C") (pintype "passive"))
      (node (ref "SJ4") (pin "2") (pinfunction "2_2") (pintype "passive"))
      (node (ref "U3") (pin "20") (pinfunction "~{CE}_20") (pintype "input"))
    )
    (net (code "137") (name "RDY_BE") (class "Default")
      (node (ref "JP1") (pin "1") (pinfunction "1_1") (pintype "passive"))
      (node (ref "JP2") (pin "1") (pinfunction "1_1") (pintype "passive"))
      (node (ref "M1") (pin "A9") (pinfunction "PK1_A9") (pintype "bidirectional"))
    )
    (net (code "138") (name "RESB") (class "Default")
      (node (ref "LED32") (pin "C") (pinfunction "C_C") (pintype "passive"))
      (node (ref "M1") (pin "A10") (pinfunction "PK2_A10") (pintype "bidirectional"))
      (node (ref "R4") (pin "2") (pinfunction "2_2") (pintype "passive"))
      (node (ref "U1") (pin "40") (pinfunction "~{RESB}_40") (pintype "input"))
      (node (ref "U4") (pin "34") (pinfunction "~{RESB}_34") (pintype "input"))
      (node (ref "X5") (pin "3") (pinfunction "3_3") (pintype "passive"))
      (node (ref "X6") (pin "1") (pinfunction "1_1") (pintype "passive"))
      (node (ref "X6") (pin "2") (pinfunction "2_2") (pintype "passive"))
    )
    (net (code "139") (name "RWB") (class "Default")
      (node (ref "LED25") (pin "A") (pinfunction "A_A") (pintype "passive"))
      (node (ref "M1") (pin "A12") (pinfunction "PK4_A12") (pintype "bidirectional"))
      (node (ref "M2") (pin "5") (pinfunction "R/W_5") (pintype "input"))
      (node (ref "U1") (pin "34") (pinfunction "R~{WB}_34") (pintype "output"))
      (node (ref "U3") (pin "27") (pinfunction "~{WE}_27") (pintype "input"))
      (node (ref "U4") (pin "22") (pinfunction "R~{WB}_22") (pintype "input"))
      (node (ref "X5") (pin "1") (pinfunction "1_1") (pintype "passive"))
    )
    (net (code "140") (name "SYNC") (class "Default")
      (node (ref "LED26") (pin "A") (pinfunction "A_A") (pintype "passive"))
      (node (ref "M1") (pin "A15") (pinfunction "PK7_A15") (pintype "bidirectional"))
      (node (ref "U1") (pin "7") (pinfunction "SYNC_7") (pintype "output"))
    )
    (net (code "141") (name "ULED1") (class "Default")
      (node (ref "LED35") (pin "A") (pinfunction "A_A") (pintype "passive"))
      (node (ref "X12") (pin "7") (pinfunction "7_7") (pintype "passive"))
    )
    (net (code "142") (name "ULED2") (class "Default")
      (node (ref "LED36") (pin "A") (pinfunction "A_A") (pintype "passive"))
      (node (ref "X12") (pin "5") (pinfunction "5_5") (pintype "passive"))
    )
    (net (code "143") (name "ULED3") (class "Default")
      (node (ref "LED37") (pin "A") (pinfunction "A_A") (pintype "passive"))
      (node (ref "X12") (pin "3") (pinfunction "3_3") (pintype "passive"))
    )
    (net (code "144") (name "ULED4") (class "Default")
      (node (ref "LED38") (pin "A") (pinfunction "A_A") (pintype "passive"))
      (node (ref "X12") (pin "1") (pinfunction "1_1") (pintype "passive"))
    )
    (net (code "145") (name "unconnected-(M1-PB0-Pad53)") (class "Default")
      (node (ref "M1") (pin "53") (pinfunction "PB0_53") (pintype "bidirectional"))
    )
    (net (code "146") (name "unconnected-(M1-PB1-Pad52)") (class "Default")
      (node (ref "M1") (pin "52") (pinfunction "PB1_52") (pintype "bidirectional"))
    )
    (net (code "147") (name "unconnected-(M1-PB2-Pad51)") (class "Default")
      (node (ref "M1") (pin "51") (pinfunction "PB2_51") (pintype "bidirectional"))
    )
    (net (code "148") (name "unconnected-(M1-PB3-Pad50)") (class "Default")
      (node (ref "M1") (pin "50") (pinfunction "PB3_50") (pintype "bidirectional"))
    )
    (net (code "149") (name "unconnected-(M1-PK0-PadA8)") (class "Default")
      (node (ref "M1") (pin "A8") (pinfunction "PK0_A8") (pintype "bidirectional"))
    )
    (net (code "150") (name "unconnected-(U1A-NC-Pad35)") (class "Default")
      (node (ref "U1") (pin "35") (pinfunction "NC_35") (pintype "no_connect"))
    )
    (net (code "151") (name "unconnected-(U1A-PHI1O-Pad3)") (class "Default")
      (node (ref "U1") (pin "3") (pinfunction "PHI1O_3") (pintype "output"))
    )
    (net (code "152") (name "unconnected-(U1A-PHI2O-Pad39)") (class "Default")
      (node (ref "U1") (pin "39") (pinfunction "PHI2O_39") (pintype "output"))
    )
    (net (code "153") (name "unconnected-(U1A-~{MLB}-Pad5)") (class "Default")
      (node (ref "U1") (pin "5") (pinfunction "~{MLB}_5") (pintype "output"))
    )
    (net (code "154") (name "unconnected-(U1A-~{VPB}-Pad1)") (class "Default")
      (node (ref "U1") (pin "1") (pinfunction "~{VPB}_1") (pintype "output"))
    )
    (net (code "155") (name "unconnected-(U4A-CA1-Pad40)") (class "Default")
      (node (ref "U4") (pin "40") (pinfunction "CA1_40") (pintype "bidirectional"))
    )
    (net (code "156") (name "unconnected-(U4A-CA2-Pad39)") (class "Default")
      (node (ref "U4") (pin "39") (pinfunction "CA2_39") (pintype "bidirectional"))
    )
    (net (code "157") (name "unconnected-(U4A-CB1-Pad18)") (class "Default")
      (node (ref "U4") (pin "18") (pinfunction "CB1_18") (pintype "bidirectional"))
    )
    (net (code "158") (name "unconnected-(U4A-CB2-Pad19)") (class "Default")
      (node (ref "U4") (pin "19") (pinfunction "CB2_19") (pintype "bidirectional"))
    )
    (net (code "159") (name "unconnected-(U6C-Y7-Pad7)") (class "Default")
      (node (ref "U6") (pin "7") (pinfunction "Y7_7") (pintype "output"))
    )
  )
)
